# Control_Sense_BOTTMOS_V2.net
KiCad netlist of a schematic drawn in Altium Designer
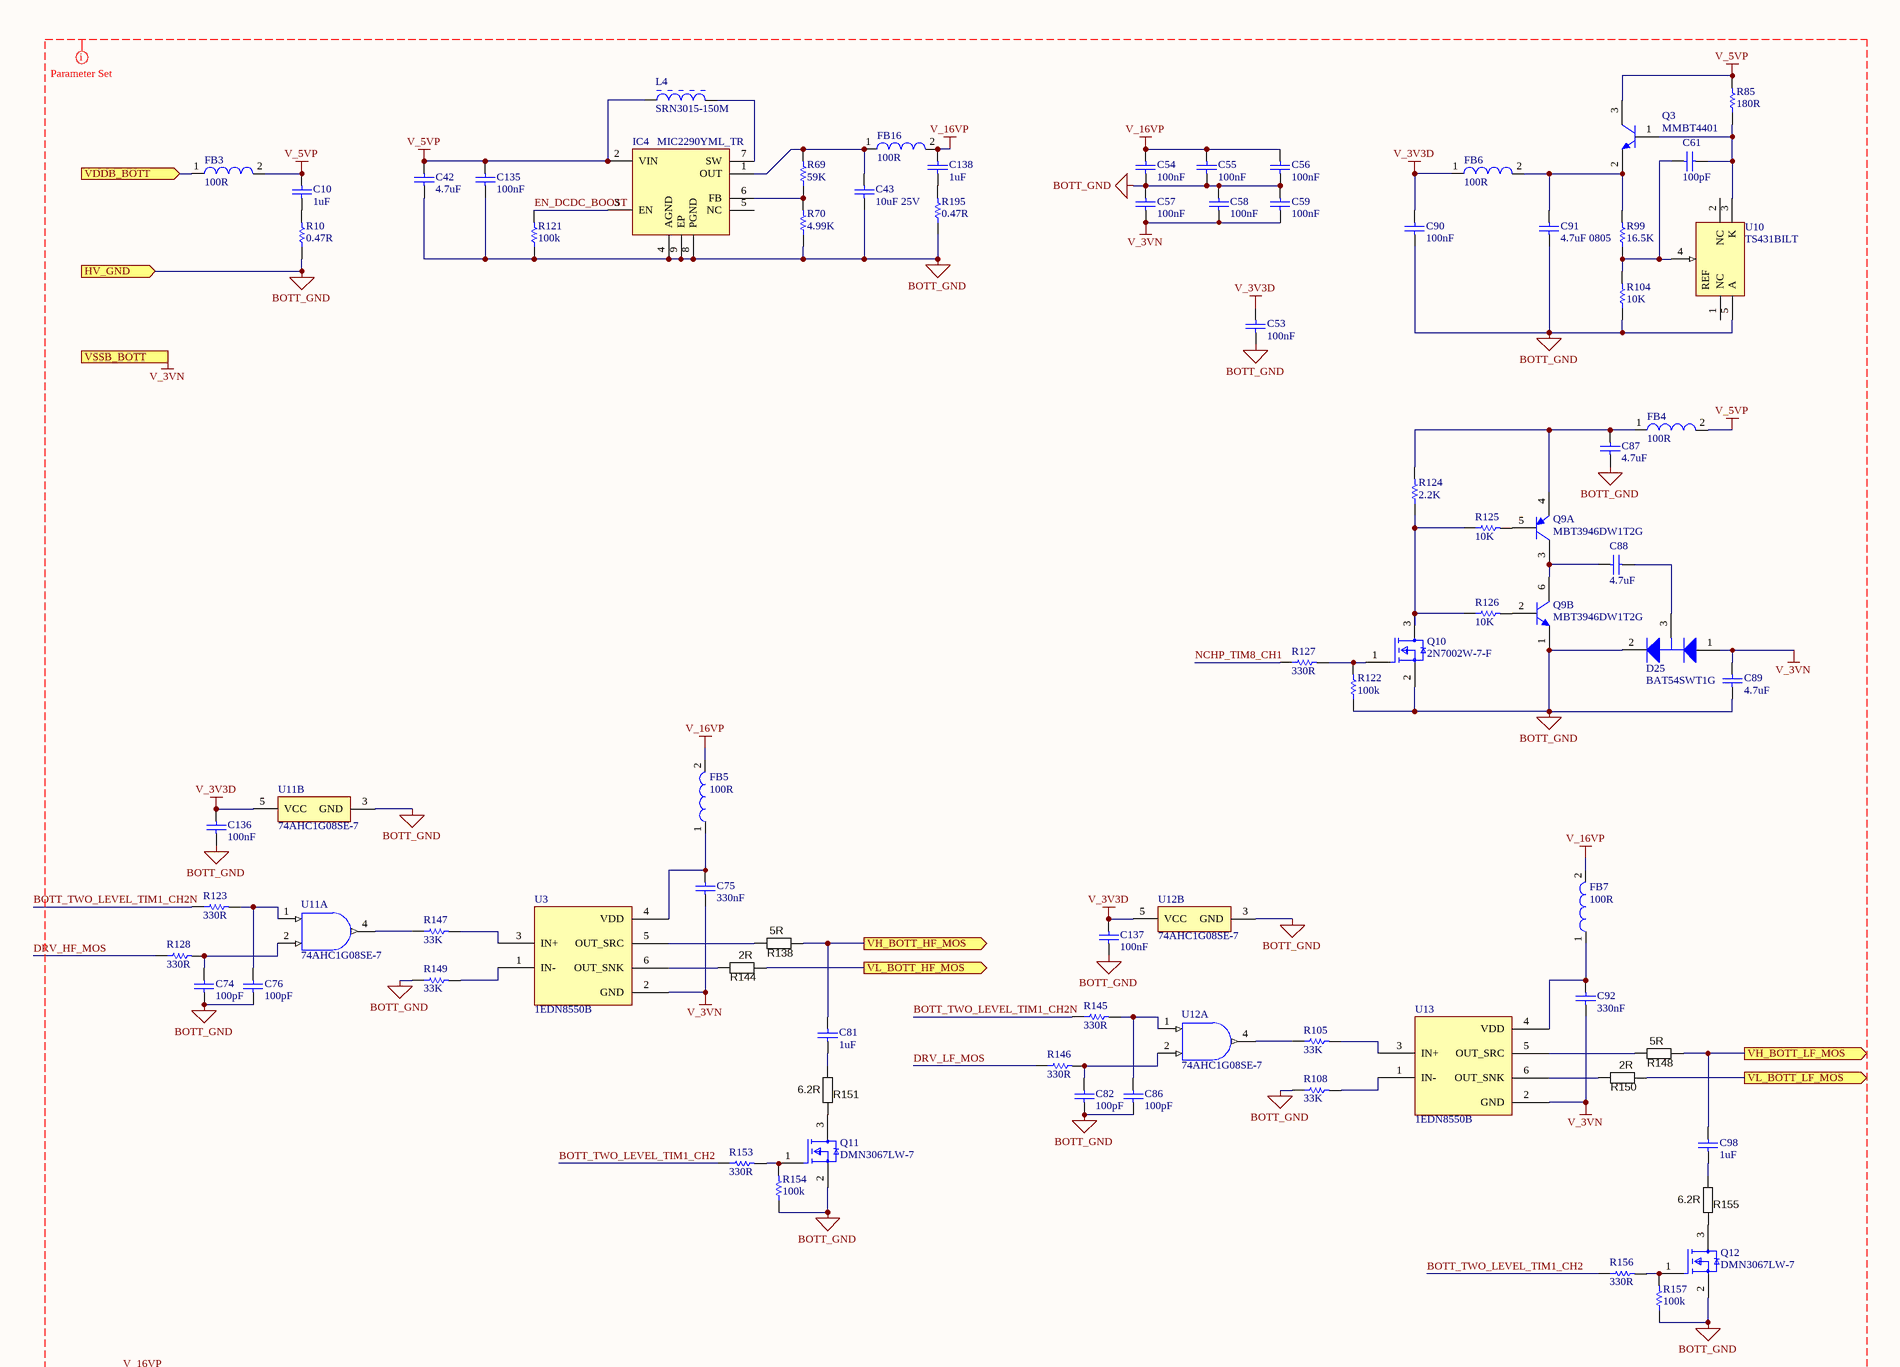
[diagram p0: Control_Sense_BOTTMOS V2.SchDoc, top]
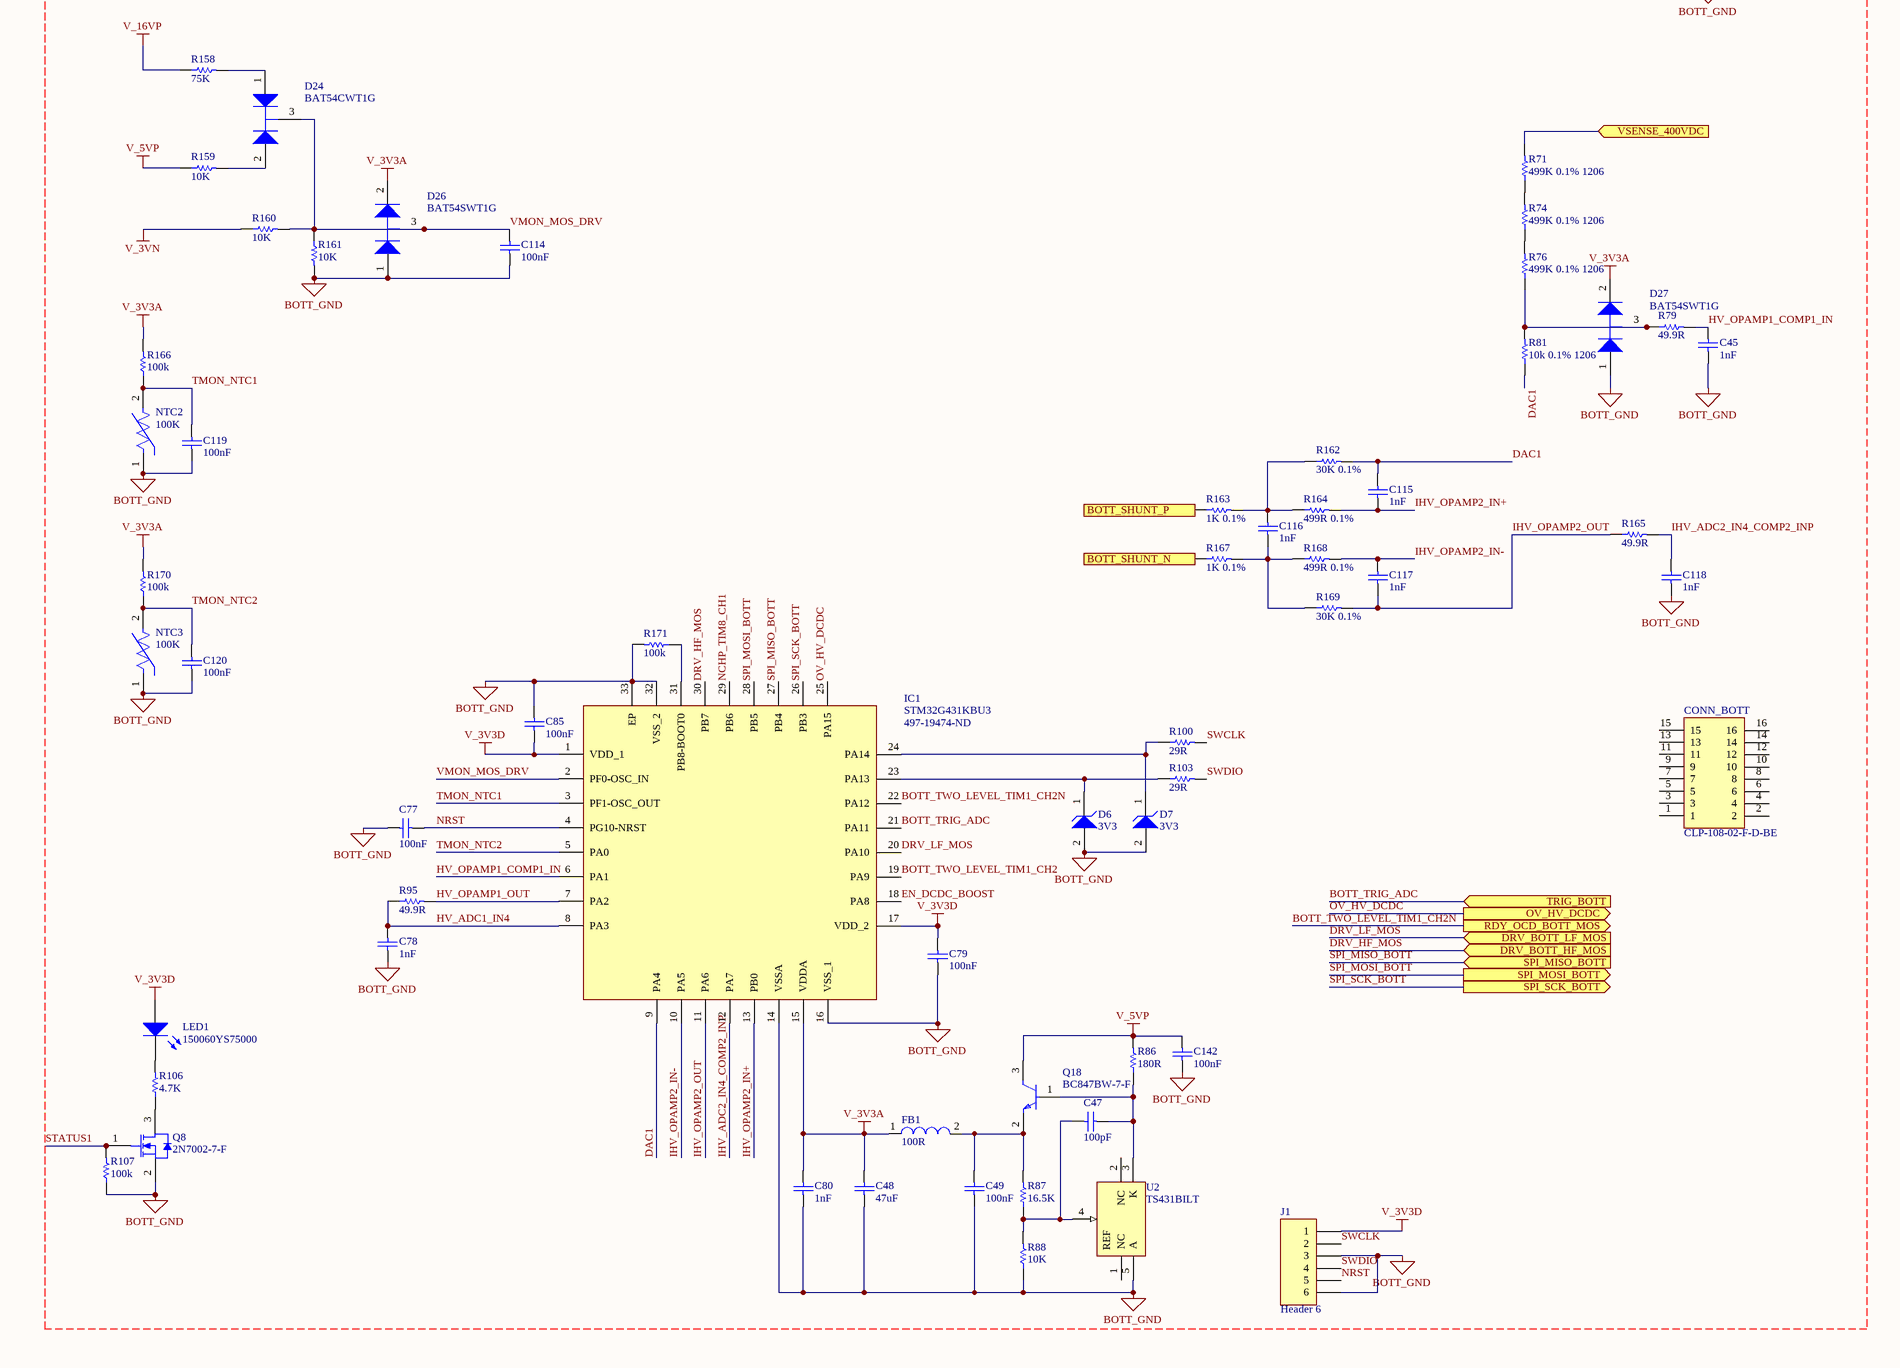
[diagram p1: Control_Sense_BOTTMOS V2.SchDoc, bottom]

(export (version "E")
  (design (tool "Eeschema 10.0.6"))
  (components
    (comp (ref "C10")
      (value "1uF")
      (footprint "CAPC2013X140X50LL20T25")
      (description "SMD Multilayer Ceramic Capacitor, 1 µF, 25 V, 0805 [2012 Metric], ± 10%, X7R")
      (fields (field (name "PART NUMBER") "C0805C105K3RACTU") (field (name "MANUFACTURER") "Kemet"))
      (libsource (lib "Altium Content Vault") (part "CAP"))
    )
    (comp (ref "C42")
      (value "4.7uF")
      (footprint "CAPC2013X145X20NL20")
      (description "Chip Capacitor, 4.7 uF, +/- 10%, 25 V, -55 to 125 degC, 0805 (2012 Metric), RoHS, Tape and Reel")
      (fields (field (name "MANUFACTURER") "TDK") (field (name "TOLERANCE") "±10%"))
      (libsource (lib "Altium Content Vault") (part "CAP-NP-2"))
    )
    (comp (ref "C43")
      (value "10uF 25V")
      (footprint "CAPC3216X229X50LL20T25")
      (description "Chip Capacitor, 10 uF, +/- 10%, 25 V, -55 to 85 degC, 1206 (3216 Metric), RoHS, Tape and Reel")
      (fields (field (name "MANUFACTURER") "AVX"))
      (libsource (lib "Altium Content Vault") (part "CAP-NP-2"))
    )
    (comp (ref "C45")
      (value "1nF")
      (footprint "CAPC1005X56X25LL10T15")
      (fields
        (field (name "MANUFACTURER") "AVX Interconnect / Elco")
        (field (name "PART NUMBER") "04025C102MAT2A")
        (field (name "TOLERANCE") "20%")
      )
      (libsource (lib "Altium Content Vault") (part "CAP"))
    )
    (comp (ref "C47")
      (value "100pF")
      (footprint "CAPC1608X90X35NL10T15")
      (description "0603 100pF 50V ±5 % Tolerance C0G SMT Multilayer Ceramic Capacitor")
      (fields (field (name "PART NUMBER") "GRM1885C1H101JA01D") (field (name "MANUFACTURER") "Murata"))
      (libsource (lib "Altium Content Vault") (part "CAP"))
    )
    (comp (ref "C48")
      (value "47uF")
      (footprint "CAPC2013X145X50LL20T25")
      (fields
        (field (name "MANUFACTURER") "Kemet")
        (field (name "PART NUMBER") "C0805C476M9PACTU")
        (field (name "TOLERANCE") "20%")
      )
      (libsource (lib "Altium Content Vault") (part "CAP"))
    )
    (comp (ref "C49")
      (value "100nF")
      (footprint "SAMS-C0603-2_N")
      (description "Cap Ceramic 0.1uF 50VDC X7R 10% SMD 0603 Paper T/R")
      (fields
        (field (name "MANUFACTURER") "Samsung Electro-Mechanics")
        (field (name "MANUFACTURER PART NUMBER") "CL10B104KB8NNNC")
      )
      (libsource (lib "Altium Content Vault") (part "CAP-NP-2"))
    )
    (comp (ref "C53")
      (value "100nF")
      (footprint "CAPC1608X90X35LL15T15")
      (fields
        (field (name "MANUFACTURER") "AVX Interconnect / Elco")
        (field (name "PART NUMBER") "06035A151JAT2A.")
        (field (name "MANUFACTURER PART NUMBER") "06035A151JAT2A")
      )
      (libsource (lib "Altium Content Vault") (part "CAP"))
    )
    (comp (ref "C54")
      (value "100nF")
      (footprint "CAPC1608X90X35NL15T15")
      (fields
        (field (name "MANUFACTURER") "AVX Interconnect / Elco")
        (field (name "PART NUMBER") "06035A151JAT2A.")
        (field (name "MANUFACTURER PART NUMBER") "06035A151JAT2A")
      )
      (libsource (lib "Altium Content Vault") (part "CAP"))
    )
    (comp (ref "C55")
      (value "100nF")
      (footprint "CAPC1608X90X35NL15T15")
      (fields
        (field (name "MANUFACTURER") "AVX Interconnect / Elco")
        (field (name "PART NUMBER") "06035A151JAT2A.")
        (field (name "MANUFACTURER PART NUMBER") "06035A151JAT2A")
      )
      (libsource (lib "Altium Content Vault") (part "CAP"))
    )
    (comp (ref "C56")
      (value "100nF")
      (footprint "CAPC1608X90X35NL15T15")
      (fields
        (field (name "MANUFACTURER") "AVX Interconnect / Elco")
        (field (name "PART NUMBER") "06035A151JAT2A.")
        (field (name "MANUFACTURER PART NUMBER") "06035A151JAT2A")
      )
      (libsource (lib "Altium Content Vault") (part "CAP"))
    )
    (comp (ref "C57")
      (value "100nF")
      (footprint "CAPC1608X90X35NL15T15")
      (fields
        (field (name "MANUFACTURER") "AVX Interconnect / Elco")
        (field (name "PART NUMBER") "06035A151JAT2A.")
        (field (name "MANUFACTURER PART NUMBER") "06035A151JAT2A")
      )
      (libsource (lib "Altium Content Vault") (part "CAP"))
    )
    (comp (ref "C58")
      (value "100nF")
      (footprint "CAPC1608X90X35NL15T15")
      (fields
        (field (name "MANUFACTURER") "AVX Interconnect / Elco")
        (field (name "PART NUMBER") "06035A151JAT2A.")
        (field (name "MANUFACTURER PART NUMBER") "06035A151JAT2A")
      )
      (libsource (lib "Altium Content Vault") (part "CAP"))
    )
    (comp (ref "C59")
      (value "100nF")
      (footprint "CAPC1608X90X35NL15T15")
      (fields
        (field (name "MANUFACTURER") "AVX Interconnect / Elco")
        (field (name "PART NUMBER") "06035A151JAT2A.")
        (field (name "MANUFACTURER PART NUMBER") "06035A151JAT2A")
      )
      (libsource (lib "Altium Content Vault") (part "CAP"))
    )
    (comp (ref "C61")
      (value "100pF")
      (footprint "CAPC1608X90X35NL10T15")
      (description "0603 100pF 50V ±5 % Tolerance C0G SMT Multilayer Ceramic Capacitor")
      (fields (field (name "PART NUMBER") "GRM1885C1H101JA01D") (field (name "MANUFACTURER") "Murata"))
      (libsource (lib "Altium Content Vault") (part "CAP"))
    )
    (comp (ref "C74")
      (value "100pF")
      (footprint "CAPC1608X90X35NL10T15")
      (fields
        (field (name "PART NUMBER") "GRM1885C1H101JA01D")
        (field (name "MANUFACTURER") "Murata")
        (field (name "TOLERANCE") "5%")
      )
      (libsource (lib "Altium Content Vault") (part "CAP"))
    )
    (comp (ref "C75")
      (value "330nF")
      (footprint "CAPC2013X135X45NL10T25")
      (description "Chip Capacitor, 0.1 uF, +/- 10%, 50 V, -55 to 125 degC, 0805 (2012 Metric), RoHS, Tape and Reel")
      (fields (field (name "VOLTAGE") "50V") (field (name "TOLERANCE") "10%"))
      (libsource (lib "Altium Content Vault") (part "CAP-NP-2"))
    )
    (comp (ref "C76")
      (value "100pF")
      (footprint "CAPC1608X90X35NL10T15")
      (fields
        (field (name "PART NUMBER") "GRM1885C1H101JA01D")
        (field (name "MANUFACTURER") "Murata")
        (field (name "TOLERANCE") "5%")
      )
      (libsource (lib "Altium Content Vault") (part "CAP"))
    )
    (comp (ref "C77")
      (value "100nF")
      (footprint "CAPC1608X90X35LL15T15")
      (fields
        (field (name "MANUFACTURER") "AVX Interconnect / Elco")
        (field (name "PART NUMBER") "06035A151JAT2A.")
        (field (name "MANUFACTURER PART NUMBER") "06035A151JAT2A")
      )
      (libsource (lib "Altium Content Vault") (part "CAP"))
    )
    (comp (ref "C78")
      (value "1nF")
      (footprint "CAPC1005X56X25LL10T15")
      (fields
        (field (name "MANUFACTURER") "AVX Interconnect / Elco")
        (field (name "PART NUMBER") "04025C102MAT2A")
        (field (name "TOLERANCE") "20%")
      )
      (libsource (lib "Altium Content Vault") (part "CAP"))
    )
    (comp (ref "C79")
      (value "100nF")
      (footprint "SAMS-C0603-2_N")
      (description "Cap Ceramic 0.1uF 50VDC X7R 10% SMD 0603 Paper T/R")
      (fields
        (field (name "MANUFACTURER") "Samsung Electro-Mechanics")
        (field (name "MANUFACTURER PART NUMBER") "CL10B104KB8NNNC")
      )
      (libsource (lib "Altium Content Vault") (part "CAP-NP-2"))
    )
    (comp (ref "C80")
      (value "1nF")
      (footprint "CAPC1005X56X25LL10T15")
      (fields
        (field (name "MANUFACTURER") "AVX Interconnect / Elco")
        (field (name "PART NUMBER") "04025C102MAT2A")
        (field (name "TOLERANCE") "20%")
      )
      (libsource (lib "Altium Content Vault") (part "CAP"))
    )
    (comp (ref "C81")
      (value "1uF")
      (footprint "CAPC2013X135X45NL10T25")
      (description "Chip Capacitor, 0.1 uF, +/- 10%, 50 V, -55 to 125 degC, 0805 (2012 Metric), RoHS, Tape and Reel")
      (fields (field (name "VOLTAGE") "50V") (field (name "TOLERANCE") "10%"))
      (libsource (lib "Altium Content Vault") (part "CAP-NP-2"))
    )
    (comp (ref "C82")
      (value "100pF")
      (footprint "CAPC1608X90X35NL10T15")
      (fields
        (field (name "PART NUMBER") "GRM1885C1H101JA01D")
        (field (name "MANUFACTURER") "Murata")
        (field (name "TOLERANCE") "5%")
      )
      (libsource (lib "Altium Content Vault") (part "CAP"))
    )
    (comp (ref "C85")
      (value "100nF")
      (footprint "CAPC1608X90X35LL15T15")
      (fields
        (field (name "MANUFACTURER") "AVX Interconnect / Elco")
        (field (name "PART NUMBER") "06035A151JAT2A.")
        (field (name "MANUFACTURER PART NUMBER") "06035A151JAT2A")
      )
      (libsource (lib "Altium Content Vault") (part "CAP"))
    )
    (comp (ref "C86")
      (value "100pF")
      (footprint "CAPC1608X90X35NL10T15")
      (fields
        (field (name "PART NUMBER") "GRM1885C1H101JA01D")
        (field (name "MANUFACTURER") "Murata")
        (field (name "TOLERANCE") "5%")
      )
      (libsource (lib "Altium Content Vault") (part "CAP"))
    )
    (comp (ref "C87")
      (value "4.7uF")
      (footprint "SAMS-C0603-2_L")
      (description "Cap Ceramic 0.1uF 50VDC X7R 10% SMD 0603 Paper T/R")
      (fields
        (field (name "MANUFACTURER") "Samsung Electro-Mechanics")
        (field (name "MANUFACTURER PART NUMBER") "CL10B104KB8NNNC")
      )
      (libsource (lib "Altium Content Vault") (part "CAP-NP-2"))
    )
    (comp (ref "C88")
      (value "4.7uF")
      (footprint "SAMS-C0603-2_L")
      (description "Cap Ceramic 0.1uF 50VDC X7R 10% SMD 0603 Paper T/R")
      (fields
        (field (name "MANUFACTURER") "Samsung Electro-Mechanics")
        (field (name "MANUFACTURER PART NUMBER") "CL10B104KB8NNNC")
      )
      (libsource (lib "Altium Content Vault") (part "CAP-NP-2"))
    )
    (comp (ref "C89")
      (value "4.7uF")
      (footprint "SAMS-C0603-2_L")
      (description "Cap Ceramic 0.1uF 50VDC X7R 10% SMD 0603 Paper T/R")
      (fields
        (field (name "MANUFACTURER") "Samsung Electro-Mechanics")
        (field (name "MANUFACTURER PART NUMBER") "CL10B104KB8NNNC")
      )
      (libsource (lib "Altium Content Vault") (part "CAP-NP-2"))
    )
    (comp (ref "C90")
      (value "100nF")
      (footprint "SAMS-C0603-2_N")
      (description "Cap Ceramic 0.1uF 50VDC X7R 10% SMD 0603 Paper T/R")
      (fields
        (field (name "MANUFACTURER") "Samsung Electro-Mechanics")
        (field (name "MANUFACTURER PART NUMBER") "CL10B104KB8NNNC")
      )
      (libsource (lib "Altium Content Vault") (part "CAP-NP-2"))
    )
    (comp (ref "C91")
      (value "4.7uF 0805")
      (footprint "CAPC2013X145X20NL20")
      (description "Chip Capacitor, 4.7 uF, +/- 10%, 25 V, -55 to 125 degC, 0805 (2012 Metric), RoHS, Tape and Reel")
      (fields (field (name "MANUFACTURER") "TDK") (field (name "TOLERANCE") "±10%"))
      (libsource (lib "Altium Content Vault") (part "CAP-NP-2"))
    )
    (comp (ref "C92")
      (value "330nF")
      (footprint "CAPC2013X135X45NL10T25")
      (description "Chip Capacitor, 0.1 uF, +/- 10%, 50 V, -55 to 125 degC, 0805 (2012 Metric), RoHS, Tape and Reel")
      (fields (field (name "VOLTAGE") "50V") (field (name "TOLERANCE") "10%"))
      (libsource (lib "Altium Content Vault") (part "CAP-NP-2"))
    )
    (comp (ref "C98")
      (value "1uF")
      (footprint "CAPC2013X135X45NL10T25")
      (description "Chip Capacitor, 0.1 uF, +/- 10%, 50 V, -55 to 125 degC, 0805 (2012 Metric), RoHS, Tape and Reel")
      (fields (field (name "VOLTAGE") "50V") (field (name "TOLERANCE") "10%"))
      (libsource (lib "Altium Content Vault") (part "CAP-NP-2"))
    )
    (comp (ref "C114")
      (value "100nF")
      (footprint "CAPC1608X90X35LL15T15")
      (fields
        (field (name "MANUFACTURER") "AVX Interconnect / Elco")
        (field (name "PART NUMBER") "06035A151JAT2A.")
        (field (name "MANUFACTURER PART NUMBER") "06035A151JAT2A")
      )
      (libsource (lib "Altium Content Vault") (part "CAP"))
    )
    (comp (ref "C115")
      (value "1nF")
      (footprint "CAPC1005X56X25LL10T15")
      (fields
        (field (name "MANUFACTURER") "AVX Interconnect / Elco")
        (field (name "PART NUMBER") "04025C102MAT2A")
        (field (name "TOLERANCE") "20%")
      )
      (libsource (lib "Altium Content Vault") (part "CAP"))
    )
    (comp (ref "C116")
      (value "1nF")
      (footprint "CAPC1608X90X35LL15T15")
      (fields
        (field (name "MANUFACTURER") "AVX Interconnect / Elco")
        (field (name "PART NUMBER") "06035A151JAT2A.")
        (field (name "MANUFACTURER PART NUMBER") "06035A151JAT2A")
      )
      (libsource (lib "Altium Content Vault") (part "CAP"))
    )
    (comp (ref "C117")
      (value "1nF")
      (footprint "CAPC1005X56X25LL10T15")
      (fields
        (field (name "MANUFACTURER") "AVX Interconnect / Elco")
        (field (name "PART NUMBER") "04025C102MAT2A")
        (field (name "TOLERANCE") "20%")
      )
      (libsource (lib "Altium Content Vault") (part "CAP"))
    )
    (comp (ref "C118")
      (value "1nF")
      (footprint "CAPC1005X56X25LL10T15")
      (fields
        (field (name "MANUFACTURER") "AVX Interconnect / Elco")
        (field (name "PART NUMBER") "04025C102MAT2A")
        (field (name "TOLERANCE") "20%")
      )
      (libsource (lib "Altium Content Vault") (part "CAP"))
    )
    (comp (ref "C119")
      (value "100nF")
      (footprint "CAPC1608X90X35LL15T15")
      (fields
        (field (name "MANUFACTURER") "AVX Interconnect / Elco")
        (field (name "PART NUMBER") "06035A151JAT2A.")
        (field (name "MANUFACTURER PART NUMBER") "06035A151JAT2A")
      )
      (libsource (lib "Altium Content Vault") (part "CAP"))
    )
    (comp (ref "C120")
      (value "100nF")
      (footprint "CAPC1608X90X35LL15T15")
      (fields
        (field (name "MANUFACTURER") "AVX Interconnect / Elco")
        (field (name "PART NUMBER") "06035A151JAT2A.")
        (field (name "MANUFACTURER PART NUMBER") "06035A151JAT2A")
      )
      (libsource (lib "Altium Content Vault") (part "CAP"))
    )
    (comp (ref "C135")
      (value "100nF")
      (footprint "CAPC1608X90X35LL15T15")
      (fields
        (field (name "MANUFACTURER") "AVX Interconnect / Elco")
        (field (name "PART NUMBER") "06035A151JAT2A.")
        (field (name "MANUFACTURER PART NUMBER") "06035A151JAT2A")
      )
      (libsource (lib "Altium Content Vault") (part "CAP"))
    )
    (comp (ref "C136")
      (value "100nF")
      (footprint "CAPC1608X90X35LL15T15")
      (fields
        (field (name "MANUFACTURER") "AVX Interconnect / Elco")
        (field (name "PART NUMBER") "06035A151JAT2A.")
        (field (name "MANUFACTURER PART NUMBER") "06035A151JAT2A")
      )
      (libsource (lib "Altium Content Vault") (part "CAP"))
    )
    (comp (ref "C137")
      (value "100nF")
      (footprint "CAPC1608X90X35LL15T15")
      (fields
        (field (name "MANUFACTURER") "AVX Interconnect / Elco")
        (field (name "PART NUMBER") "06035A151JAT2A.")
        (field (name "MANUFACTURER PART NUMBER") "06035A151JAT2A")
      )
      (libsource (lib "Altium Content Vault") (part "CAP"))
    )
    (comp (ref "C138")
      (value "1uF")
      (footprint "CAPC2013X140X50LL20T25")
      (description "SMD Multilayer Ceramic Capacitor, 1 µF, 25 V, 0805 [2012 Metric], ± 10%, X7R")
      (fields (field (name "PART NUMBER") "C0805C105K3RACTU") (field (name "MANUFACTURER") "Kemet"))
      (libsource (lib "Altium Content Vault") (part "CAP"))
    )
    (comp (ref "C142")
      (value "100nF")
      (footprint "SAMS-C0603-2_N")
      (description "Cap Ceramic 0.1uF 50VDC X7R 10% SMD 0603 Paper T/R")
      (fields
        (field (name "MANUFACTURER") "Samsung Electro-Mechanics")
        (field (name "MANUFACTURER PART NUMBER") "CL10B104KB8NNNC")
      )
      (libsource (lib "Altium Content Vault") (part "CAP-NP-2"))
    )
    (comp (ref "CONN_BOTT")
      (value "CLP-108-02-F-D-BE")
      (footprint "SamacSys:CLP-108-02-XXX-D-BE")
      (description "Connector")
      (fields (field (name "MOUSER PART NUMBER") "200-CLP10802FDBE"))
      (libsource (lib "*") (part "CLP-108-02-F-D-BE"))
    )
    (comp (ref "D6")
      (value "3V3")
      (footprint "ONSC-SOD-523-2-502-01_V")
      (fields (field (name "MANUFACTURER") "On Semiconductor") (field (name "PARTNUMBER") "ESD5Z3.3T1G"))
      (libsource (lib "Altium Content Vault") (part "ONSC-K1A2-2"))
    )
    (comp (ref "D7")
      (value "3V3")
      (footprint "ONSC-SOD-523-2-502-01_V")
      (fields (field (name "MANUFACTURER") "On Semiconductor") (field (name "PARTNUMBER") "ESD5Z3.3T1G"))
      (libsource (lib "Altium Content Vault") (part "ONSC-K1A2-2"))
    )
    (comp (ref "D24")
      (value "BAT54CWT1G")
      (footprint "ONSC-SOT-323-3-419-04_V")
      (description "Dual Series Cathode Schottky Barrier Diodes, 3-Pin SOT-323, Pb-Free, Tape and Reel")
      (fields (field (name "MANUFACTURER") "On Semiconductor"))
      (libsource (lib "Altium Content Vault") (part "ONSC-D-A1A2K3-3"))
    )
    (comp (ref "D25")
      (value "BAT54SWT1G")
      (footprint "ONSC-SOT-323-3-419-04_V")
      (description "Dual Series Schottky Barrier Diodes, 3-Pin SOT-323, Pb-Free, Tape and Reel")
      (fields (field (name "MANUFACTURER") "On Semiconductor"))
      (libsource (lib "Altium Content Vault") (part "ONSC-D-A1K2C3-3"))
    )
    (comp (ref "D26")
      (value "BAT54SWT1G")
      (footprint "ONSC-SOT-323-3-419-04_V")
      (description "Dual Series Schottky Barrier Diodes, 3-Pin SOT-323, Pb-Free, Tape and Reel")
      (fields (field (name "MANUFACTURER") "On Semiconductor"))
      (libsource (lib "Altium Content Vault") (part "ONSC-D-A1K2C3-3"))
    )
    (comp (ref "D27")
      (value "BAT54SWT1G")
      (footprint "ONSC-SOT-323-3-419-04_V")
      (description "Dual Series Schottky Barrier Diodes, 3-Pin SOT-323, Pb-Free, Tape and Reel")
      (fields (field (name "MANUFACTURER") "On Semiconductor"))
      (libsource (lib "Altium Content Vault") (part "ONSC-D-A1K2C3-3"))
    )
    (comp (ref "FB1")
      (value "100R")
      (footprint "SMD-0603")
      (description "SMD EMI Suppression Ferrite Bead WE-CBF, Z = 1500 Ohm")
      (libsource (lib "Altium Content Vault") (part "PAS-IND-INDUCTOR-2"))
    )
    (comp (ref "FB3")
      (value "100R")
      (footprint "SMD-0603")
      (description "SMD EMI Suppression Ferrite Bead WE-CBF, Z = 1500 Ohm")
      (libsource (lib "Altium Content Vault") (part "PAS-IND-INDUCTOR-2"))
    )
    (comp (ref "FB4")
      (value "100R")
      (footprint "SMD-0603")
      (description "SMD EMI Suppression Ferrite Bead WE-CBF, Z = 1500 Ohm")
      (libsource (lib "Altium Content Vault") (part "PAS-IND-INDUCTOR-2"))
    )
    (comp (ref "FB5")
      (value "100R")
      (footprint "SMD-0603")
      (description "SMD EMI Suppression Ferrite Bead WE-CBF, Z = 1500 Ohm")
      (libsource (lib "Altium Content Vault") (part "PAS-IND-INDUCTOR-2"))
    )
    (comp (ref "FB6")
      (value "100R")
      (footprint "SMD-0603")
      (description "SMD EMI Suppression Ferrite Bead WE-CBF, Z = 1500 Ohm")
      (libsource (lib "Altium Content Vault") (part "PAS-IND-INDUCTOR-2"))
    )
    (comp (ref "FB7")
      (value "100R")
      (footprint "SMD-0603")
      (description "SMD EMI Suppression Ferrite Bead WE-CBF, Z = 1500 Ohm")
      (libsource (lib "Altium Content Vault") (part "PAS-IND-INDUCTOR-2"))
    )
    (comp (ref "FB16")
      (value "100R")
      (footprint "SMD-0603")
      (description "SMD EMI Suppression Ferrite Bead WE-CBF, Z = 1500 Ohm")
      (libsource (lib "Altium Content Vault") (part "PAS-IND-INDUCTOR-2"))
    )
    (comp (ref "IC1")
      (value "STM32G431KBU3")
      (footprint "SamacSys:QFN50P500X500X60-33N-D")
      (description "Microcontroller 32-Bit ARM Cortex-M4 RISC 128KB Flash 1.71V to 3.6V 32-Pin UFQFPN")
      (fields
        (field (name "MOUSER PART NUMBER") "511-STM32G431KBU3")
        (field (name "MANUFACTURER") "STMicroelectronics")
        (field (name "SUPPLIER PART NUMBER 1") "497-19474-ND")
      )
      (libsource (lib "SamacSys") (part "STM32G431KBU3"))
    )
    (comp (ref "IC4")
      (value "MIC2290YML_TR")
      (footprint "SamacSys:SON50P200X200X95-9N-D")
      (description "Integrated Circuit")
      (fields (field (name "MANUFACTURER_PART_NUMBER") "MIC2290YML TR"))
      (libsource (lib "*") (part "MIC2290YML_TR"))
    )
    (comp (ref "J1")
      (value "Header 6")
      (footprint "HDR1X6")
      (description "Header, 6-Pin")
      (fields (field (name "PUBLISHER") "Altium Limited"))
      (libsource (lib "Miscellaneous Connectors") (part "Header 6"))
    )
    (comp (ref "L4")
      (value "SRN3015-150M")
      (footprint "BOUR-SRN3015-2_V")
      (fields (field (name "MANUFACTURER") "Bourns") (field (name "TOLERANCE") "20%"))
      (libsource (lib "Altium Content Vault") (part "BOUR-IND-2A"))
    )
    (comp (ref "LED1")
      (value "150060YS75000")
      (footprint "0603_A")
      (description "SMD mono-color Chip LED, WL-SMCW, Yellow")
      (fields (field (name "MANUFACTURER") "Wuerth Elektronik"))
      (libsource (lib "Altium Content Vault") (part "WE-LED_K1A2-2"))
    )
    (comp (ref "NTC2")
      (value "100K")
      (footprint "FP-NXR_151B030-MFG")
      (description "Thermistor NTC 10kΩ ±1% 2-Pin Radial Bulk")
      (fields (field (name "TOLERANCE") "1%"))
      (libsource (lib "Altium Content Vault") (part "3b148a6ebabc5fb4d708a66c052d352"))
    )
    (comp (ref "NTC3")
      (value "100K")
      (footprint "FP-NXR_151B030-MFG")
      (description "Thermistor NTC 10kΩ ±1% 2-Pin Radial Bulk")
      (fields (field (name "TOLERANCE") "1%"))
      (libsource (lib "Altium Content Vault") (part "3b148a6ebabc5fb4d708a66c052d352"))
    )
    (comp (ref "Q3")
      (value "MMBT4401")
      (footprint "FAIR-SOT23-3_V")
      (description "NPN General-Purpose Amplifier, 0.6 A, 40 V, -55 to 150 degC, 3-Pin SOT-23, RoHS, Tape and Reel")
      (fields (field (name "MANUFACTURER") "FairchildSemiconductor"))
      (libsource (lib "Altium Content Vault") (part "BJT-NPN-BEC-3"))
    )
    (comp (ref "Q8")
      (value "2N7002-7-F")
      (footprint "DIOD-SOT23-3_V")
      (fields (field (name "MANUFACTURER") "DiodesIncorporated"))
      (libsource (lib "Altium Content Vault") (part "NEMOS-GSD-3"))
    )
    (comp (ref "Q9")
      (value "MBT3946DW1T2G")
      (footprint "ONSC-SC70-6-419B-02_W_V")
      (description "Complementary General Purpose Transistors, 6-Pin SC70, Pb-Free, Tape and Reel")
      (fields (field (name "MANUFACTURER") "On Semiconductor"))
      (libsource (lib "Altium Content Vault") (part "ONSC-NPN_PNP-6"))
    )
    (comp (ref "Q10")
      (value "2N7002W-7-F")
      (footprint "FP-SOT323-IPC_C")
      (description "MOSFET N-CH 60V 115MA SOT323")
      (libsource (lib "Altium Content Vault") (part "381a366367e4312d0f7d2747150cb42"))
    )
    (comp (ref "Q11")
      (value "DMN3067LW-7")
      (footprint "FP-SOT323-IPC_C")
      (description "MOSFET N-CH 60V 115MA SOT323")
      (libsource (lib "Altium Content Vault") (part "381a366367e4312d0f7d2747150cb42"))
    )
    (comp (ref "Q12")
      (value "DMN3067LW-7")
      (footprint "FP-SOT323-IPC_C")
      (description "MOSFET N-CH 60V 115MA SOT323")
      (libsource (lib "Altium Content Vault") (part "381a366367e4312d0f7d2747150cb42"))
    )
    (comp (ref "Q18")
      (value "BC847BW-7-F")
      (footprint "FP-SOT323-IPC_C")
      (description "TRANS NPN 45V 0.1A SC70-3")
      (fields
        (field (name "OCTOPART") "https://octopart.com/bc847bw-7-f-diodes+inc.-354380")
        (field (name "MANUFACTURER") "Diodes Inc")
      )
      (libsource (lib "Altium Content Vault") (part "b44e953556f554d0102664c7d152cb4"))
    )
    (comp (ref "R10")
      (value "0.47R")
      (footprint "RESC1608X55X25ML10T15")
      (description "Chip Resistor, 0 Ohm, +/- 5%, 0.1 W, -55 to 155 degC, 0603 (1608 Metric), RoHS, Tape and Reel")
      (fields (field (name "TOLERANCE") "5%") (field (name "MANUFACTURER") "Yageo"))
      (libsource (lib "Altium Content Vault") (part "RES-2"))
    )
    (comp (ref "R69")
      (value "59K")
      (footprint "RESC1608X55X30NL15T15")
      (fields
        (field (name "MANUFACTURER") "Panasonic")
        (field (name "PART NUMBER") "ERJ-3EKF5902V")
        (field (name "TOLERANCE") "1%")
      )
      (libsource (lib "Altium Content Vault") (part "RES"))
    )
    (comp (ref "R70")
      (value "4.99K")
      (footprint "RESC1609X50X30NL10T20")
      (fields
        (field (name "MANUFACTURER") "Vishay Dale")
        (field (name "PART NUMBER") "CRCW06034K99FKTA")
        (field (name "TOLERANCE") "1%")
      )
      (libsource (lib "Altium Content Vault") (part "RES"))
    )
    (comp (ref "R71")
      (value "499K 0.1% 1206")
      (footprint "RESC3216X50X50NL20T25")
      (description "RES SMD 499K OHM 0.1% 1/4W 1206")
      (fields (field (name "MANUFACTURER") "Susumu") (field (name "PART NUMBER") "RG3216P-4993-B-T1"))
      (libsource (lib "Altium Content Vault") (part "RES"))
    )
    (comp (ref "R74")
      (value "499K 0.1% 1206")
      (footprint "RESC3216X50X50NL20T25")
      (description "RES SMD 499K OHM 0.1% 1/4W 1206")
      (fields (field (name "MANUFACTURER") "Susumu") (field (name "PART NUMBER") "RG3216P-4993-B-T1"))
      (libsource (lib "Altium Content Vault") (part "RES"))
    )
    (comp (ref "R76")
      (value "499K 0.1% 1206")
      (footprint "RESC3216X50X50NL20T25")
      (description "RES SMD 499K OHM 0.1% 1/4W 1206")
      (fields (field (name "MANUFACTURER") "Susumu") (field (name "PART NUMBER") "RG3216P-4993-B-T1"))
      (libsource (lib "Altium Content Vault") (part "RES"))
    )
    (comp (ref "R79")
      (value "49.9R")
      (footprint "RESC1005X40X25NL05T05")
      (fields (field (name "MANUFACTURER") "Panasonic") (field (name "PART NUMBER") "ERJ-2RKF49R9X"))
      (libsource (lib "Altium Content Vault") (part "RES"))
    )
    (comp (ref "R81")
      (value "10k 0.1% 1206")
      (footprint "RESC3216X50X50NL20T20")
      (fields (field (name "MANUFACTURER") "Susumu") (field (name "PART NUMBER") "RG3216P-1002-B-T5"))
      (libsource (lib "Altium Content Vault") (part "RES"))
    )
    (comp (ref "R85")
      (value "180R")
      (footprint "RESC1608X55X25LL10T15")
      (description "Chip Resistor, 180 Ohm, +/- 1%, 0.1 W, -55 to 155 degC, 0603 (1608 Metric), RoHS, Tape and Reel")
      (fields (field (name "TOLERANCE") "1%") (field (name "MANUFACTURER") "Yageo"))
      (libsource (lib "Altium Content Vault") (part "RES-2"))
    )
    (comp (ref "R86")
      (value "180R")
      (footprint "RESC1608X55X25LL10T15")
      (description "Chip Resistor, 180 Ohm, +/- 1%, 0.1 W, -55 to 155 degC, 0603 (1608 Metric), RoHS, Tape and Reel")
      (fields (field (name "TOLERANCE") "1%") (field (name "MANUFACTURER") "Yageo"))
      (libsource (lib "Altium Content Vault") (part "RES-2"))
    )
    (comp (ref "R87")
      (value "16.5K")
      (footprint "RESC1608X55X30NL15T15")
      (description "RES, 16K5, 1%, 0.1W, 0603, THICK FILM")
      (fields (field (name "MANUFACTURER") "Panasonic") (field (name "PART NUMBER") "ERJ-3EKF1652V"))
      (libsource (lib "Altium Content Vault") (part "RES"))
    )
    (comp (ref "R88")
      (value "10K")
      (footprint "RESC1609X55X30NL15T15")
      (description "Chip Resistor, 10 KOhm, +/- 1%, 0.1 W, -55 to 155 degC, 0603 (1608 Metric), RoHS, Tape and Reel")
      (fields (field (name "TOLERANCE") "1%") (field (name "MANUFACTURER") "Panasonic"))
      (libsource (lib "Altium Content Vault") (part "RES-2"))
    )
    (comp (ref "R95")
      (value "49.9R")
      (footprint "RESC1005X40X25NL05T05")
      (fields (field (name "MANUFACTURER") "Panasonic") (field (name "PART NUMBER") "ERJ-2RKF49R9X"))
      (libsource (lib "Altium Content Vault") (part "RES"))
    )
    (comp (ref "R99")
      (value "16.5K")
      (footprint "RESC1608X55X30NL15T15")
      (description "RES, 16K5, 1%, 0.1W, 0603, THICK FILM")
      (fields (field (name "MANUFACTURER") "Panasonic") (field (name "PART NUMBER") "ERJ-3EKF1652V"))
      (libsource (lib "Altium Content Vault") (part "RES"))
    )
    (comp (ref "R100")
      (value "29R")
      (footprint "RESC1608X55X30NL20T10")
      (description "RK73B1JTTD103J")
      (fields (field (name "MANUFACTURER") "KOA Speer") (field (name "TOLERANCE") "5%"))
      (libsource (lib "Altium Content Vault") (part "RES"))
    )
    (comp (ref "R103")
      (value "29R")
      (footprint "RESC1608X55X30NL20T10")
      (description "RK73B1JTTD103J")
      (fields (field (name "MANUFACTURER") "KOA Speer") (field (name "TOLERANCE") "5%"))
      (libsource (lib "Altium Content Vault") (part "RES"))
    )
    (comp (ref "R104")
      (value "10K")
      (footprint "RESC1609X55X30LL15T15")
      (description "Chip Resistor, 10 KOhm, +/- 1%, 0.1 W, -55 to 155 degC, 0603 (1608 Metric), RoHS, Tape and Reel")
      (fields (field (name "TOLERANCE") "1%") (field (name "MANUFACTURER") "Panasonic"))
      (libsource (lib "Altium Content Vault") (part "RES-2"))
    )
    (comp (ref "R105")
      (value "33K")
      (footprint "RESC1005X40X25ML05T05")
      (fields
        (field (name "PART NUMBER") "ERJ2RKF3302X")
        (field (name "MANUFACTURER") "Panasonic")
        (field (name "MANUFACTURER PART NUMBER") "ERJ-2RKF3302X")
      )
      (libsource (lib "Altium Content Vault") (part "RES"))
    )
    (comp (ref "R106")
      (value "4.7K")
      (footprint "RESC1608X55X25ML10T15")
      (fields
        (field (name "MANUFACTURER") "Yageo")
        (field (name "MANUFACTURER PART NUMBER") "RC0603FR-07470RL")
        (field (name "TOLERANCE") "1%")
      )
      (libsource (lib "Altium Content Vault") (part "RES-2"))
    )
    (comp (ref "R107")
      (value "100k")
      (footprint "RESC1608X55X25ML10T15")
      (fields
        (field (name "MANUFACTURER") "Yageo")
        (field (name "MANUFACTURER PART NUMBER") "RC0603JR-071ML")
        (field (name "TOLERANCE") "5%")
      )
      (libsource (lib "Altium Content Vault") (part "RES-2"))
    )
    (comp (ref "R108")
      (value "33K")
      (footprint "RESC1005X40X25ML05T05")
      (fields
        (field (name "PART NUMBER") "ERJ2RKF3302X")
        (field (name "MANUFACTURER") "Panasonic")
        (field (name "MANUFACTURER PART NUMBER") "ERJ-2RKF3302X")
      )
      (libsource (lib "Altium Content Vault") (part "RES"))
    )
    (comp (ref "R121")
      (value "100k")
      (footprint "RESC1608X55X30NL15T15")
      (description "Res Thick Film 0603 100K Ohm 1% 0.1W(1/10W) ±100ppm/C Pad SMD Automotive T/R")
      (fields (field (name "PART NUMBER") "ERJ-3EKF1003V") (field (name "MANUFACTURER") "Panasonic"))
      (libsource (lib "Altium Content Vault") (part "RES"))
    )
    (comp (ref "R122")
      (value "100k")
      (footprint "RESC1608X55X30NL15T15")
      (description "Res Thick Film 0603 100K Ohm 1% 0.1W(1/10W) ±100ppm/C Pad SMD Automotive T/R")
      (fields (field (name "PART NUMBER") "ERJ-3EKF1003V") (field (name "MANUFACTURER") "Panasonic"))
      (libsource (lib "Altium Content Vault") (part "RES"))
    )
    (comp (ref "R123")
      (value "330R")
      (footprint "RESC1608X55X25NL10T15")
      (description "Chip Resistor, 330 Ohm, +/- 1%, 0.1 W, -55 to 155 degC, 0603 (1608 Metric), RoHS, Tape and Reel")
      (fields (field (name "TOLERANCE") "10%"))
      (libsource (lib "Altium Content Vault") (part "RES-2"))
    )
    (comp (ref "R124")
      (value "2.2K")
      (footprint "RESC1608X55X25NL10T15")
      (fields
        (field (name "TOLERANCE") "1%")
        (field (name "MANUFACTURER") "Yageo")
        (field (name "MANUFACTURER PART NUMBER") "RC0603FR-072K2L")
      )
      (libsource (lib "Altium Content Vault") (part "RES-2"))
    )
    (comp (ref "R125")
      (value "10K")
      (footprint "RESC1608X55X30NL20T10")
      (description "RK73B1JTTD103J")
      (fields (field (name "MANUFACTURER") "KOA Speer") (field (name "TOLERANCE") "5%"))
      (libsource (lib "Altium Content Vault") (part "RES"))
    )
    (comp (ref "R126")
      (value "10K")
      (footprint "RESC1608X55X30NL20T10")
      (description "RK73B1JTTD103J")
      (fields (field (name "MANUFACTURER") "KOA Speer") (field (name "TOLERANCE") "5%"))
      (libsource (lib "Altium Content Vault") (part "RES"))
    )
    (comp (ref "R127")
      (value "330R")
      (footprint "RESC1608X55X25NL10T15")
      (description "Chip Resistor, 330 Ohm, +/- 1%, 0.1 W, -55 to 155 degC, 0603 (1608 Metric), RoHS, Tape and Reel")
      (fields (field (name "TOLERANCE") "10%"))
      (libsource (lib "Altium Content Vault") (part "RES-2"))
    )
    (comp (ref "R128")
      (value "330R")
      (footprint "RESC1608X55X25NL10T15")
      (description "Chip Resistor, 330 Ohm, +/- 1%, 0.1 W, -55 to 155 degC, 0603 (1608 Metric), RoHS, Tape and Reel")
      (fields (field (name "TOLERANCE") "10%"))
      (libsource (lib "Altium Content Vault") (part "RES-2"))
    )
    (comp (ref "R138")
      (value "5R")
      (footprint "RESC2012X70N")
      (description "Resistor, 0805 SMD, Empty footprint")
      (libsource (lib "PBL - Resistors") (part "RES_EMPTY_0805"))
    )
    (comp (ref "R144")
      (value "2R")
      (footprint "RESC2012X70N")
      (description "Resistor, 0805 SMD, Empty footprint")
      (libsource (lib "PBL - Resistors") (part "RES_EMPTY_0805"))
    )
    (comp (ref "R145")
      (value "330R")
      (footprint "RESC1608X55X25NL10T15")
      (description "Chip Resistor, 330 Ohm, +/- 1%, 0.1 W, -55 to 155 degC, 0603 (1608 Metric), RoHS, Tape and Reel")
      (fields (field (name "TOLERANCE") "10%"))
      (libsource (lib "Altium Content Vault") (part "RES-2"))
    )
    (comp (ref "R146")
      (value "330R")
      (footprint "RESC1608X55X25NL10T15")
      (description "Chip Resistor, 330 Ohm, +/- 1%, 0.1 W, -55 to 155 degC, 0603 (1608 Metric), RoHS, Tape and Reel")
      (fields (field (name "TOLERANCE") "10%"))
      (libsource (lib "Altium Content Vault") (part "RES-2"))
    )
    (comp (ref "R147")
      (value "33K")
      (footprint "RESC1005X40X25ML05T05")
      (fields
        (field (name "PART NUMBER") "ERJ2RKF3302X")
        (field (name "MANUFACTURER") "Panasonic")
        (field (name "MANUFACTURER PART NUMBER") "ERJ-2RKF3302X")
      )
      (libsource (lib "Altium Content Vault") (part "RES"))
    )
    (comp (ref "R148")
      (value "5R")
      (footprint "RESC2012X70N")
      (description "Resistor, 0805 SMD, Empty footprint")
      (libsource (lib "PBL - Resistors") (part "RES_EMPTY_0805"))
    )
    (comp (ref "R149")
      (value "33K")
      (footprint "RESC1005X40X25ML05T05")
      (fields
        (field (name "PART NUMBER") "ERJ2RKF3302X")
        (field (name "MANUFACTURER") "Panasonic")
        (field (name "MANUFACTURER PART NUMBER") "ERJ-2RKF3302X")
      )
      (libsource (lib "Altium Content Vault") (part "RES"))
    )
    (comp (ref "R150")
      (value "2R")
      (footprint "RESC2012X70N")
      (description "Resistor, 0805 SMD, Empty footprint")
      (libsource (lib "PBL - Resistors") (part "RES_EMPTY_0805"))
    )
    (comp (ref "R151")
      (value "6.2R")
      (footprint "RESC2012X70N")
      (description "Resistor, 0805 SMD, Empty footprint")
      (libsource (lib "") (part "RES_EMPTY_0805_1"))
    )
    (comp (ref "R153")
      (value "330R")
      (footprint "RESC1608X55X25NL10T15")
      (description "Chip Resistor, 330 Ohm, +/- 1%, 0.1 W, -55 to 155 degC, 0603 (1608 Metric), RoHS, Tape and Reel")
      (fields (field (name "TOLERANCE") "10%"))
      (libsource (lib "Altium Content Vault") (part "RES-2"))
    )
    (comp (ref "R154")
      (value "100k")
      (footprint "RESC1608X55X30NL15T15")
      (description "Res Thick Film 0603 100K Ohm 1% 0.1W(1/10W) ±100ppm/C Pad SMD Automotive T/R")
      (fields (field (name "PART NUMBER") "ERJ-3EKF1003V") (field (name "MANUFACTURER") "Panasonic"))
      (libsource (lib "Altium Content Vault") (part "RES"))
    )
    (comp (ref "R155")
      (value "6.2R")
      (footprint "RESC2012X70N")
      (description "Resistor, 0805 SMD, Empty footprint")
      (libsource (lib "") (part "RES_EMPTY_0805_1"))
    )
    (comp (ref "R156")
      (value "330R")
      (footprint "RESC1608X55X25NL10T15")
      (description "Chip Resistor, 330 Ohm, +/- 1%, 0.1 W, -55 to 155 degC, 0603 (1608 Metric), RoHS, Tape and Reel")
      (fields (field (name "TOLERANCE") "10%"))
      (libsource (lib "Altium Content Vault") (part "RES-2"))
    )
    (comp (ref "R157")
      (value "100k")
      (footprint "RESC1608X55X30NL15T15")
      (description "Res Thick Film 0603 100K Ohm 1% 0.1W(1/10W) ±100ppm/C Pad SMD Automotive T/R")
      (fields (field (name "PART NUMBER") "ERJ-3EKF1003V") (field (name "MANUFACTURER") "Panasonic"))
      (libsource (lib "Altium Content Vault") (part "RES"))
    )
    (comp (ref "R158")
      (value "75K")
      (footprint "RESC1608X55X30NL15T15")
      (fields
        (field (name "PART NUMBER") "ERJ-3EKF7502V")
        (field (name "MANUFACTURER") "Panasonic")
        (field (name "TOLERANCE") "1%")
      )
      (libsource (lib "Altium Content Vault") (part "RES"))
    )
    (comp (ref "R159")
      (value "10K")
      (footprint "RESC1608X55X30NL20T10")
      (description "RK73B1JTTD103J")
      (fields (field (name "MANUFACTURER") "KOA Speer") (field (name "TOLERANCE") "5%"))
      (libsource (lib "Altium Content Vault") (part "RES"))
    )
    (comp (ref "R160")
      (value "10K")
      (footprint "RESC1608X55X30NL20T10")
      (description "RK73B1JTTD103J")
      (fields (field (name "MANUFACTURER") "KOA Speer") (field (name "TOLERANCE") "5%"))
      (libsource (lib "Altium Content Vault") (part "RES"))
    )
    (comp (ref "R161")
      (value "10K")
      (footprint "RESC1608X55X30NL20T10")
      (description "RK73B1JTTD103J")
      (fields (field (name "MANUFACTURER") "KOA Speer") (field (name "TOLERANCE") "5%"))
      (libsource (lib "Altium Content Vault") (part "RES"))
    )
    (comp (ref "R162")
      (value "30K 0.1%")
      (footprint "RESC1608X55N")
      (description "Resistor, SMD 30 kOhm 0603  ±  0.1 %, ERA3AEB303V, Panasonic Automotive & Industrial Systems")
      (fields (field (name "MANUFACTURER") "Panasonic") (field (name "PART NUMBER") "ERA3AEB303V"))
      (libsource (lib "PBL - Resistors") (part "RES"))
    )
    (comp (ref "R163")
      (value "1K 0.1%")
      (footprint "RESC1608X55X25NL10T15")
      (description "RES SMD 1K OHM 0.1% 1/10W 0603")
      (fields (field (name "PART NUMBER") "RT0603BRE071KL") (field (name "MANUFACTURER") "Yageo"))
      (libsource (lib "Altium Content Vault") (part "RES"))
    )
    (comp (ref "R164")
      (value "499R 0.1%")
      (footprint "RESC1608X55N")
      (description "Res Thin Film 0603 499 Ohm 0.1% 1/10W ±25ppm/°C Molded SMD SMD Punched Carrier T/R")
      (fields (field (name "PART NUMBER") "ERA3AEB4990V") (field (name "MANUFACTURER") "Panasonic"))
      (libsource (lib "PBL - Resistors") (part "RES"))
    )
    (comp (ref "R165")
      (value "49.9R")
      (footprint "RESC1005X40X25NL05T05")
      (fields (field (name "MANUFACTURER") "Panasonic") (field (name "PART NUMBER") "ERJ-2RKF49R9X"))
      (libsource (lib "Altium Content Vault") (part "RES"))
    )
    (comp (ref "R166")
      (value "100k")
      (footprint "RESC1608X55X30NL15T15")
      (description "Res Thick Film 0603 100K Ohm 1% 0.1W(1/10W) ±100ppm/C Pad SMD Automotive T/R")
      (fields (field (name "PART NUMBER") "ERJ-3EKF1003V") (field (name "MANUFACTURER") "Panasonic"))
      (libsource (lib "Altium Content Vault") (part "RES"))
    )
    (comp (ref "R167")
      (value "1K 0.1%")
      (footprint "RESC1608X55X25NL10T15")
      (description "RES SMD 1K OHM 0.1% 1/10W 0603")
      (fields (field (name "PART NUMBER") "RT0603BRE071KL") (field (name "MANUFACTURER") "Yageo"))
      (libsource (lib "Altium Content Vault") (part "RES"))
    )
    (comp (ref "R168")
      (value "499R 0.1%")
      (footprint "RESC1608X55N")
      (description "Res Thin Film 0603 499 Ohm 0.1% 1/10W ±25ppm/°C Molded SMD SMD Punched Carrier T/R")
      (fields (field (name "PART NUMBER") "ERA3AEB4990V") (field (name "MANUFACTURER") "Panasonic"))
      (libsource (lib "PBL - Resistors") (part "RES"))
    )
    (comp (ref "R169")
      (value "30K 0.1%")
      (footprint "RESC1608X55N")
      (description "Resistor, SMD 30 kOhm 0603  ±  0.1 %, ERA3AEB303V, Panasonic Automotive & Industrial Systems")
      (fields (field (name "MANUFACTURER") "Panasonic") (field (name "PART NUMBER") "ERA3AEB303V"))
      (libsource (lib "PBL - Resistors") (part "RES"))
    )
    (comp (ref "R170")
      (value "100k")
      (footprint "RESC1608X55X30NL15T15")
      (description "Res Thick Film 0603 100K Ohm 1% 0.1W(1/10W) ±100ppm/C Pad SMD Automotive T/R")
      (fields (field (name "PART NUMBER") "ERJ-3EKF1003V") (field (name "MANUFACTURER") "Panasonic"))
      (libsource (lib "Altium Content Vault") (part "RES"))
    )
    (comp (ref "R171")
      (value "100k")
      (footprint "RESC1608X55X30NL15T15")
      (description "Res Thick Film 0603 100K Ohm 1% 0.1W(1/10W) ±100ppm/C Pad SMD Automotive T/R")
      (fields (field (name "PART NUMBER") "ERJ-3EKF1003V") (field (name "MANUFACTURER") "Panasonic"))
      (libsource (lib "Altium Content Vault") (part "RES"))
    )
    (comp (ref "R195")
      (value "0.47R")
      (footprint "RESC1608X55X25ML10T15")
      (description "Chip Resistor, 0 Ohm, +/- 5%, 0.1 W, -55 to 155 degC, 0603 (1608 Metric), RoHS, Tape and Reel")
      (fields (field (name "TOLERANCE") "5%") (field (name "MANUFACTURER") "Yageo"))
      (libsource (lib "Altium Content Vault") (part "RES-2"))
    )
    (comp (ref "U2")
      (value "TS431BILT")
      (footprint "SOT23-5_N")
      (description "30mA, Low voltage adjustable shunt reference, 1.24 to 6V, 5-Pin SOT23-5, Tape and Reel")
      (libsource (lib "Altium Content Vault") (part "PM-REF-431-IL5"))
    )
    (comp (ref "U3")
      (value "1EDN8550B")
      (footprint "SOT23-6")
      (description "Single-channel EiceDRIVER™ with true  differential inputs")
      (libsource (lib "1EDN8550B") (part "1EDN8550B"))
    )
    (comp (ref "U10")
      (value "TS431BILT")
      (footprint "SOT23-5_N")
      (description "30mA, Low voltage adjustable shunt reference, 1.24 to 6V, 5-Pin SOT23-5, Tape and Reel")
      (libsource (lib "Altium Content Vault") (part "PM-REF-431-IL5"))
    )
    (comp (ref "U11")
      (value "74AHC1G08SE-7")
      (footprint "DCK0005A_M")
      (description "Single 2-Input Positive-AND Gate, DCK0005A, SMALL T&R")
      (fields
        (field (name "GENERIC PART NUMBER") "SN74AHC1G08")
        (field (name "MANUFACTURER") "Texas Instruments")
      )
      (libsource (lib "Altium Content Vault") (part "TI-SN74XXX1X08-5"))
    )
    (comp (ref "U12")
      (value "74AHC1G08SE-7")
      (footprint "DCK0005A_M")
      (description "Single 2-Input Positive-AND Gate, DCK0005A, SMALL T&R")
      (fields
        (field (name "GENERIC PART NUMBER") "SN74AHC1G08")
        (field (name "MANUFACTURER") "Texas Instruments")
      )
      (libsource (lib "Altium Content Vault") (part "TI-SN74XXX1X08-5"))
    )
    (comp (ref "U13")
      (value "1EDN8550B")
      (footprint "SOT23-6")
      (description "Single-channel EiceDRIVER™ with true  differential inputs")
      (libsource (lib "1EDN8550B") (part "1EDN8550B"))
    )
  )
  (nets
    (net (code "1") (name "/BOTT_SHUNT_N") (class "Default")
      (node (ref "R167") (pin "1") (pinfunction "1_1") (pintype "passive"))
    )
    (net (code "2") (name "/BOTT_SHUNT_P") (class "Default")
      (node (ref "R163") (pin "1") (pinfunction "1_1") (pintype "passive"))
    )
    (net (code "3") (name "/BOTT_TRIG_ADC") (class "Default")
      (node (ref "IC1") (pin "21") (pinfunction "PA11_21") (pintype "passive"))
    )
    (net (code "4") (name "/BOTT_TWO_LEVEL_TIM1_CH2") (class "Default")
      (node (ref "IC1") (pin "19") (pinfunction "PA9_19") (pintype "passive"))
      (node (ref "R153") (pin "1") (pinfunction "1_1") (pintype "passive"))
      (node (ref "R156") (pin "1") (pinfunction "1_1") (pintype "passive"))
    )
    (net (code "5") (name "/BOTT_TWO_LEVEL_TIM1_CH2N") (class "Default")
      (node (ref "IC1") (pin "22") (pinfunction "PA12_22") (pintype "passive"))
      (node (ref "R123") (pin "1") (pinfunction "1_1") (pintype "passive"))
      (node (ref "R145") (pin "1") (pinfunction "1_1") (pintype "passive"))
    )
    (net (code "6") (name "/DAC1") (class "Default")
      (node (ref "C115") (pin "2") (pinfunction "2_2") (pintype "passive"))
      (node (ref "IC1") (pin "9") (pinfunction "PA4_9") (pintype "passive"))
      (node (ref "R162") (pin "2") (pinfunction "2_2") (pintype "passive"))
      (node (ref "R81") (pin "1") (pinfunction "1_1") (pintype "passive"))
    )
    (net (code "7") (name "/DRV_HF_MOS") (class "Default")
      (node (ref "IC1") (pin "30") (pinfunction "PB7_30") (pintype "passive"))
      (node (ref "R128") (pin "1") (pinfunction "1_1") (pintype "passive"))
    )
    (net (code "8") (name "/DRV_LF_MOS") (class "Default")
      (node (ref "IC1") (pin "20") (pinfunction "PA10_20") (pintype "passive"))
      (node (ref "R146") (pin "1") (pinfunction "1_1") (pintype "passive"))
    )
    (net (code "9") (name "/EN_DCDC_BOOST") (class "Default")
      (node (ref "IC1") (pin "18") (pinfunction "PA8_18") (pintype "passive"))
      (node (ref "IC4") (pin "3") (pinfunction "EN_3") (pintype "passive"))
      (node (ref "R121") (pin "2") (pinfunction "2_2") (pintype "passive"))
    )
    (net (code "10") (name "/HV_ADC1_IN4") (class "Default")
      (node (ref "C78") (pin "2") (pinfunction "2_2") (pintype "passive"))
      (node (ref "IC1") (pin "8") (pinfunction "PA3_8") (pintype "passive"))
      (node (ref "R95") (pin "1") (pinfunction "1_1") (pintype "passive"))
    )
    (net (code "11") (name "/HV_OPAMP1_COMP1_IN") (class "Default")
      (node (ref "C45") (pin "2") (pinfunction "2_2") (pintype "passive"))
      (node (ref "IC1") (pin "6") (pinfunction "PA1_6") (pintype "passive"))
      (node (ref "R79") (pin "2") (pinfunction "2_2") (pintype "passive"))
    )
    (net (code "12") (name "/HV_OPAMP1_OUT") (class "Default")
      (node (ref "IC1") (pin "7") (pinfunction "PA2_7") (pintype "passive"))
      (node (ref "R95") (pin "2") (pinfunction "2_2") (pintype "passive"))
    )
    (net (code "13") (name "/IHV_ADC2_IN4_COMP2_INP") (class "Default")
      (node (ref "C118") (pin "2") (pinfunction "2_2") (pintype "passive"))
      (node (ref "IC1") (pin "12") (pinfunction "PA7_12") (pintype "passive"))
      (node (ref "R165") (pin "2") (pinfunction "2_2") (pintype "passive"))
    )
    (net (code "14") (name "/IHV_OPAMP2_IN+") (class "Default")
      (node (ref "C115") (pin "1") (pinfunction "1_1") (pintype "passive"))
      (node (ref "IC1") (pin "13") (pinfunction "PB0_13") (pintype "passive"))
      (node (ref "R164") (pin "2") (pinfunction "2_2") (pintype "passive"))
    )
    (net (code "15") (name "/IHV_OPAMP2_IN-") (class "Default")
      (node (ref "C117") (pin "2") (pinfunction "2_2") (pintype "passive"))
      (node (ref "IC1") (pin "10") (pinfunction "PA5_10") (pintype "passive"))
      (node (ref "R168") (pin "2") (pinfunction "2_2") (pintype "passive"))
    )
    (net (code "16") (name "/IHV_OPAMP2_OUT") (class "Default")
      (node (ref "C117") (pin "1") (pinfunction "1_1") (pintype "passive"))
      (node (ref "IC1") (pin "11") (pinfunction "PA6_11") (pintype "passive"))
      (node (ref "R165") (pin "1") (pinfunction "1_1") (pintype "passive"))
      (node (ref "R169") (pin "2") (pinfunction "2_2") (pintype "passive"))
    )
    (net (code "17") (name "/NCHP_TIM8_CH1") (class "Default")
      (node (ref "IC1") (pin "29") (pinfunction "PB6_29") (pintype "passive"))
      (node (ref "R127") (pin "1") (pinfunction "1_1") (pintype "passive"))
    )
    (net (code "18") (name "/NRST") (class "Default")
      (node (ref "C77") (pin "2") (pinfunction "2_2") (pintype "passive"))
      (node (ref "IC1") (pin "4") (pinfunction "PG10-NRST_4") (pintype "passive"))
      (node (ref "J1") (pin "5") (pinfunction "5_5") (pintype "passive"))
    )
    (net (code "19") (name "/OV_HV_DCDC") (class "Default")
      (node (ref "IC1") (pin "25") (pinfunction "PA15_25") (pintype "passive"))
    )
    (net (code "20") (name "/SPI_MISO_BOTT") (class "Default")
      (node (ref "IC1") (pin "27") (pinfunction "PB4_27") (pintype "passive"))
    )
    (net (code "21") (name "/SPI_MOSI_BOTT") (class "Default")
      (node (ref "IC1") (pin "28") (pinfunction "PB5_28") (pintype "passive"))
    )
    (net (code "22") (name "/SPI_SCK_BOTT") (class "Default")
      (node (ref "IC1") (pin "26") (pinfunction "PB3_26") (pintype "passive"))
    )
    (net (code "23") (name "/STATUS1") (class "Default")
      (node (ref "Q8") (pin "1") (pinfunction "G_1") (pintype "passive"))
      (node (ref "R107") (pin "2") (pinfunction "2_2") (pintype "passive"))
    )
    (net (code "24") (name "/SWCLK") (class "Default")
      (node (ref "J1") (pin "2") (pinfunction "2_2") (pintype "passive"))
      (node (ref "R100") (pin "2") (pinfunction "2_2") (pintype "passive"))
    )
    (net (code "25") (name "/SWDIO") (class "Default")
      (node (ref "J1") (pin "4") (pinfunction "4_4") (pintype "passive"))
      (node (ref "R103") (pin "2") (pinfunction "2_2") (pintype "passive"))
    )
    (net (code "26") (name "/TMON_NTC1") (class "Default")
      (node (ref "C119") (pin "2") (pinfunction "2_2") (pintype "passive"))
      (node (ref "IC1") (pin "3") (pinfunction "PF1-OSC_OUT_3") (pintype "passive"))
      (node (ref "NTC2") (pin "2") (pinfunction "2_2") (pintype "passive"))
      (node (ref "R166") (pin "1") (pinfunction "1_1") (pintype "passive"))
    )
    (net (code "27") (name "/TMON_NTC2") (class "Default")
      (node (ref "C120") (pin "2") (pinfunction "2_2") (pintype "passive"))
      (node (ref "IC1") (pin "5") (pinfunction "PA0_5") (pintype "passive"))
      (node (ref "NTC3") (pin "2") (pinfunction "2_2") (pintype "passive"))
      (node (ref "R170") (pin "1") (pinfunction "1_1") (pintype "passive"))
    )
    (net (code "28") (name "/VDDB_BOTT") (class "Default")
      (node (ref "FB3") (pin "1") (pinfunction "1_1") (pintype "passive"))
    )
    (net (code "29") (name "/VH_BOTT_HF_MOS") (class "Default")
      (node (ref "C81") (pin "2") (pinfunction "2_2") (pintype "passive"))
      (node (ref "R138") (pin "2") (pinfunction "2_2") (pintype "passive"))
    )
    (net (code "30") (name "/VH_BOTT_LF_MOS") (class "Default")
      (node (ref "C98") (pin "2") (pinfunction "2_2") (pintype "passive"))
      (node (ref "R148") (pin "2") (pinfunction "2_2") (pintype "passive"))
    )
    (net (code "31") (name "/VL_BOTT_HF_MOS") (class "Default")
      (node (ref "R144") (pin "2") (pinfunction "2_2") (pintype "passive"))
    )
    (net (code "32") (name "/VL_BOTT_LF_MOS") (class "Default")
      (node (ref "R150") (pin "2") (pinfunction "2_2") (pintype "passive"))
    )
    (net (code "33") (name "/VMON_MOS_DRV") (class "Default")
      (node (ref "C114") (pin "2") (pinfunction "2_2") (pintype "passive"))
      (node (ref "D24") (pin "3") (pinfunction "K_3") (pintype "passive"))
      (node (ref "D26") (pin "3") (pinfunction "K/A_3") (pintype "passive"))
      (node (ref "IC1") (pin "2") (pinfunction "PF0-OSC_IN_2") (pintype "passive"))
      (node (ref "R160") (pin "2") (pinfunction "2_2") (pintype "passive"))
      (node (ref "R161") (pin "1") (pinfunction "1_1") (pintype "passive"))
    )
    (net (code "34") (name "/VSENSE_400VDC") (class "Default")
      (node (ref "R71") (pin "2") (pinfunction "2_2") (pintype "passive"))
    )
    (net (code "35") (name "BOTT_GND") (class "Default")
      (node (ref "C114") (pin "1") (pinfunction "1_1") (pintype "passive"))
      (node (ref "C118") (pin "1") (pinfunction "1_1") (pintype "passive"))
      (node (ref "C119") (pin "1") (pinfunction "1_1") (pintype "passive"))
      (node (ref "C120") (pin "1") (pinfunction "1_1") (pintype "passive"))
      (node (ref "C135") (pin "1") (pinfunction "1_1") (pintype "passive"))
      (node (ref "C136") (pin "1") (pinfunction "1_1") (pintype "passive"))
      (node (ref "C137") (pin "1") (pinfunction "1_1") (pintype "passive"))
      (node (ref "C142") (pin "1") (pinfunction "1_1") (pintype "passive"))
      (node (ref "C42") (pin "1") (pinfunction "1_1") (pintype "passive"))
      (node (ref "C43") (pin "1") (pinfunction "1_1") (pintype "passive"))
      (node (ref "C45") (pin "1") (pinfunction "1_1") (pintype "passive"))
      (node (ref "C48") (pin "1") (pinfunction "1_1") (pintype "passive"))
      (node (ref "C49") (pin "1") (pinfunction "1_1") (pintype "passive"))
      (node (ref "C53") (pin "1") (pinfunction "1_1") (pintype "passive"))
      (node (ref "C54") (pin "1") (pinfunction "1_1") (pintype "passive"))
      (node (ref "C55") (pin "1") (pinfunction "1_1") (pintype "passive"))
      (node (ref "C56") (pin "1") (pinfunction "1_1") (pintype "passive"))
      (node (ref "C57") (pin "2") (pinfunction "2_2") (pintype "passive"))
      (node (ref "C58") (pin "2") (pinfunction "2_2") (pintype "passive"))
      (node (ref "C59") (pin "2") (pinfunction "2_2") (pintype "passive"))
      (node (ref "C74") (pin "1") (pinfunction "1_1") (pintype "passive"))
      (node (ref "C76") (pin "1") (pinfunction "1_1") (pintype "passive"))
      (node (ref "C77") (pin "1") (pinfunction "1_1") (pintype "passive"))
      (node (ref "C78") (pin "1") (pinfunction "1_1") (pintype "passive"))
      (node (ref "C79") (pin "1") (pinfunction "1_1") (pintype "passive"))
      (node (ref "C80") (pin "1") (pinfunction "1_1") (pintype "passive"))
      (node (ref "C82") (pin "1") (pinfunction "1_1") (pintype "passive"))
      (node (ref "C85") (pin "2") (pinfunction "2_2") (pintype "passive"))
      (node (ref "C86") (pin "1") (pinfunction "1_1") (pintype "passive"))
      (node (ref "C87") (pin "1") (pinfunction "1_1") (pintype "passive"))
      (node (ref "C89") (pin "1") (pinfunction "1_1") (pintype "passive"))
      (node (ref "C90") (pin "1") (pinfunction "1_1") (pintype "passive"))
      (node (ref "C91") (pin "1") (pinfunction "1_1") (pintype "passive"))
      (node (ref "D25") (pin "2") (pinfunction "K_2") (pintype "passive"))
      (node (ref "D26") (pin "1") (pinfunction "A_1") (pintype "passive"))
      (node (ref "D27") (pin "1") (pinfunction "A_1") (pintype "passive"))
      (node (ref "D6") (pin "2") (pinfunction "A_2") (pintype "passive"))
      (node (ref "D7") (pin "2") (pinfunction "A_2") (pintype "passive"))
      (node (ref "IC1") (pin "14") (pinfunction "VSSA_14") (pintype "passive"))
      (node (ref "IC1") (pin "16") (pinfunction "VSS_1_16") (pintype "passive"))
      (node (ref "IC1") (pin "32") (pinfunction "VSS_2_32") (pintype "passive"))
      (node (ref "IC1") (pin "33") (pinfunction "EP_33") (pintype "passive"))
      (node (ref "IC4") (pin "4") (pinfunction "AGND_4") (pintype "passive"))
      (node (ref "IC4") (pin "8") (pinfunction "PGND_8") (pintype "passive"))
      (node (ref "IC4") (pin "9") (pinfunction "EP_9") (pintype "passive"))
      (node (ref "J1") (pin "3") (pinfunction "3_3") (pintype "passive"))
      (node (ref "J1") (pin "6") (pinfunction "6_6") (pintype "passive"))
      (node (ref "NTC2") (pin "1") (pinfunction "1_1") (pintype "passive"))
      (node (ref "NTC3") (pin "1") (pinfunction "1_1") (pintype "passive"))
      (node (ref "Q10") (pin "2") (pinfunction "S_2") (pintype "passive"))
      (node (ref "Q11") (pin "2") (pinfunction "S_2") (pintype "passive"))
      (node (ref "Q12") (pin "2") (pinfunction "S_2") (pintype "passive"))
      (node (ref "Q8") (pin "2") (pinfunction "S_2") (pintype "passive"))
      (node (ref "Q9") (pin "1") (pinfunction "E_1") (pintype "passive"))
      (node (ref "R10") (pin "1") (pinfunction "1_1") (pintype "passive"))
      (node (ref "R104") (pin "1") (pinfunction "1_1") (pintype "passive"))
      (node (ref "R107") (pin "1") (pinfunction "1_1") (pintype "passive"))
      (node (ref "R108") (pin "1") (pinfunction "1_1") (pintype "passive"))
      (node (ref "R121") (pin "1") (pinfunction "1_1") (pintype "passive"))
      (node (ref "R122") (pin "1") (pinfunction "1_1") (pintype "passive"))
      (node (ref "R149") (pin "1") (pinfunction "1_1") (pintype "passive"))
      (node (ref "R154") (pin "1") (pinfunction "1_1") (pintype "passive"))
      (node (ref "R157") (pin "1") (pinfunction "1_1") (pintype "passive"))
      (node (ref "R161") (pin "2") (pinfunction "2_2") (pintype "passive"))
      (node (ref "R171") (pin "2") (pinfunction "2_2") (pintype "passive"))
      (node (ref "R195") (pin "1") (pinfunction "1_1") (pintype "passive"))
      (node (ref "R70") (pin "1") (pinfunction "1_1") (pintype "passive"))
      (node (ref "R88") (pin "1") (pinfunction "1_1") (pintype "passive"))
      (node (ref "U10") (pin "5") (pinfunction "A_5") (pintype "passive"))
      (node (ref "U11") (pin "3") (pinfunction "GND_3") (pintype "power_in"))
      (node (ref "U12") (pin "3") (pinfunction "GND_3") (pintype "power_in"))
      (node (ref "U2") (pin "5") (pinfunction "A_5") (pintype "passive"))
    )
    (net (code "36") (name "Net-(C10-Pad1)") (class "Default")
      (node (ref "C10") (pin "1") (pinfunction "1_1") (pintype "passive"))
      (node (ref "R10") (pin "2") (pinfunction "2_2") (pintype "passive"))
    )
    (net (code "37") (name "Net-(C81-Pad1)") (class "Default")
      (node (ref "C81") (pin "1") (pinfunction "1_1") (pintype "passive"))
      (node (ref "R151") (pin "2") (pinfunction "2_2") (pintype "passive"))
    )
    (net (code "38") (name "Net-(C98-Pad1)") (class "Default")
      (node (ref "C98") (pin "1") (pinfunction "1_1") (pintype "passive"))
      (node (ref "R155") (pin "2") (pinfunction "2_2") (pintype "passive"))
    )
    (net (code "39") (name "Net-(C116-Pad1)") (class "Default")
      (node (ref "C116") (pin "1") (pinfunction "1_1") (pintype "passive"))
      (node (ref "R167") (pin "2") (pinfunction "2_2") (pintype "passive"))
      (node (ref "R168") (pin "1") (pinfunction "1_1") (pintype "passive"))
      (node (ref "R169") (pin "1") (pinfunction "1_1") (pintype "passive"))
    )
    (net (code "40") (name "Net-(C116-Pad2)") (class "Default")
      (node (ref "C116") (pin "2") (pinfunction "2_2") (pintype "passive"))
      (node (ref "R162") (pin "1") (pinfunction "1_1") (pintype "passive"))
      (node (ref "R163") (pin "2") (pinfunction "2_2") (pintype "passive"))
      (node (ref "R164") (pin "1") (pinfunction "1_1") (pintype "passive"))
    )
    (net (code "41") (name "Net-(C138-Pad1)") (class "Default")
      (node (ref "C138") (pin "1") (pinfunction "1_1") (pintype "passive"))
      (node (ref "R195") (pin "2") (pinfunction "2_2") (pintype "passive"))
    )
    (net (code "42") (name "Net-(D6-K)") (class "Default")
      (node (ref "D6") (pin "1") (pinfunction "K_1") (pintype "passive"))
      (node (ref "IC1") (pin "23") (pinfunction "PA13_23") (pintype "passive"))
      (node (ref "R103") (pin "1") (pinfunction "1_1") (pintype "passive"))
    )
    (net (code "43") (name "Net-(D7-K)") (class "Default")
      (node (ref "D7") (pin "1") (pinfunction "K_1") (pintype "passive"))
      (node (ref "IC1") (pin "24") (pinfunction "PA14_24") (pintype "passive"))
      (node (ref "R100") (pin "1") (pinfunction "1_1") (pintype "passive"))
    )
    (net (code "44") (name "Net-(D24-A1)") (class "Default")
      (node (ref "D24") (pin "1") (pinfunction "A1_1") (pintype "passive"))
      (node (ref "R158") (pin "2") (pinfunction "2_2") (pintype "passive"))
    )
    (net (code "45") (name "Net-(D24-A2)") (class "Default")
      (node (ref "D24") (pin "2") (pinfunction "A2_2") (pintype "passive"))
      (node (ref "R159") (pin "2") (pinfunction "2_2") (pintype "passive"))
    )
    (net (code "46") (name "Net-(D25-K{slash}A)") (class "Default")
      (node (ref "C88") (pin "1") (pinfunction "1_1") (pintype "passive"))
      (node (ref "D25") (pin "3") (pinfunction "K/A_3") (pintype "passive"))
    )
    (net (code "47") (name "Net-(D27-K{slash}A)") (class "Default")
      (node (ref "D27") (pin "3") (pinfunction "K/A_3") (pintype "passive"))
      (node (ref "R76") (pin "1") (pinfunction "1_1") (pintype "passive"))
      (node (ref "R79") (pin "1") (pinfunction "1_1") (pintype "passive"))
      (node (ref "R81") (pin "2") (pinfunction "2_2") (pintype "passive"))
    )
    (net (code "48") (name "Net-(IC1-PB8-BOOT0)") (class "Default")
      (node (ref "IC1") (pin "31") (pinfunction "PB8-BOOT0_31") (pintype "passive"))
      (node (ref "R171") (pin "1") (pinfunction "1_1") (pintype "passive"))
    )
    (net (code "49") (name "Net-(IC4-FB)") (class "Default")
      (node (ref "IC4") (pin "6") (pinfunction "FB_6") (pintype "passive"))
      (node (ref "R69") (pin "1") (pinfunction "1_1") (pintype "passive"))
      (node (ref "R70") (pin "2") (pinfunction "2_2") (pintype "passive"))
    )
    (net (code "50") (name "Net-(IC4-OUT)") (class "Default")
      (node (ref "C43") (pin "2") (pinfunction "2_2") (pintype "passive"))
      (node (ref "FB16") (pin "1") (pinfunction "1_1") (pintype "passive"))
      (node (ref "IC4") (pin "1") (pinfunction "OUT_1") (pintype "passive"))
      (node (ref "R69") (pin "2") (pinfunction "2_2") (pintype "passive"))
    )
    (net (code "51") (name "Net-(IC4-SW)") (class "Default")
      (node (ref "IC4") (pin "7") (pinfunction "SW_7") (pintype "passive"))
      (node (ref "L4") (pin "2") (pinfunction "2_2") (pintype "passive"))
    )
    (net (code "52") (name "Net-(LED1-K)") (class "Default")
      (node (ref "LED1") (pin "1") (pinfunction "K_1") (pintype "passive"))
      (node (ref "R106") (pin "2") (pinfunction "2_2") (pintype "passive"))
    )
    (net (code "53") (name "Net-(Q3-B)") (class "Default")
      (node (ref "C61") (pin "2") (pinfunction "2_2") (pintype "passive"))
      (node (ref "Q3") (pin "1") (pinfunction "B_1") (pintype "passive"))
      (node (ref "R85") (pin "1") (pinfunction "1_1") (pintype "passive"))
      (node (ref "U10") (pin "3") (pinfunction "K_3") (pintype "passive"))
    )
    (net (code "54") (name "Net-(Q3-E)") (class "Default")
      (node (ref "C91") (pin "2") (pinfunction "2_2") (pintype "passive"))
      (node (ref "FB6") (pin "2") (pinfunction "2_2") (pintype "passive"))
      (node (ref "Q3") (pin "2") (pinfunction "E_2") (pintype "passive"))
      (node (ref "R99") (pin "2") (pinfunction "2_2") (pintype "passive"))
    )
    (net (code "55") (name "Net-(Q8-D)") (class "Default")
      (node (ref "Q8") (pin "3") (pinfunction "D_3") (pintype "passive"))
      (node (ref "R106") (pin "1") (pinfunction "1_1") (pintype "passive"))
    )
    (net (code "56") (name "Net-(Q9A-B)") (class "Default")
      (node (ref "Q9") (pin "5") (pinfunction "B_5") (pintype "passive"))
      (node (ref "R125") (pin "2") (pinfunction "2_2") (pintype "passive"))
    )
    (net (code "57") (name "Net-(Q9A-C)") (class "Default")
      (node (ref "C88") (pin "2") (pinfunction "2_2") (pintype "passive"))
      (node (ref "Q9") (pin "3") (pinfunction "C_3") (pintype "passive"))
      (node (ref "Q9") (pin "6") (pinfunction "C_6") (pintype "passive"))
    )
    (net (code "58") (name "Net-(Q9A-E)") (class "Default")
      (node (ref "C87") (pin "2") (pinfunction "2_2") (pintype "passive"))
      (node (ref "FB4") (pin "1") (pinfunction "1_1") (pintype "passive"))
      (node (ref "Q9") (pin "4") (pinfunction "E_4") (pintype "passive"))
      (node (ref "R124") (pin "2") (pinfunction "2_2") (pintype "passive"))
    )
    (net (code "59") (name "Net-(Q9B-B)") (class "Default")
      (node (ref "Q9") (pin "2") (pinfunction "B_2") (pintype "passive"))
      (node (ref "R126") (pin "2") (pinfunction "2_2") (pintype "passive"))
    )
    (net (code "60") (name "Net-(Q10-D)") (class "Default")
      (node (ref "Q10") (pin "3") (pinfunction "D_3") (pintype "passive"))
      (node (ref "R124") (pin "1") (pinfunction "1_1") (pintype "passive"))
      (node (ref "R125") (pin "1") (pinfunction "1_1") (pintype "passive"))
      (node (ref "R126") (pin "1") (pinfunction "1_1") (pintype "passive"))
    )
    (net (code "61") (name "Net-(Q10-G)") (class "Default")
      (node (ref "Q10") (pin "1") (pinfunction "G_1") (pintype "passive"))
      (node (ref "R122") (pin "2") (pinfunction "2_2") (pintype "passive"))
      (node (ref "R127") (pin "2") (pinfunction "2_2") (pintype "passive"))
    )
    (net (code "62") (name "Net-(Q11-D)") (class "Default")
      (node (ref "Q11") (pin "3") (pinfunction "D_3") (pintype "passive"))
      (node (ref "R151") (pin "1") (pinfunction "1_1") (pintype "passive"))
    )
    (net (code "63") (name "Net-(Q11-G)") (class "Default")
      (node (ref "Q11") (pin "1") (pinfunction "G_1") (pintype "passive"))
      (node (ref "R153") (pin "2") (pinfunction "2_2") (pintype "passive"))
      (node (ref "R154") (pin "2") (pinfunction "2_2") (pintype "passive"))
    )
    (net (code "64") (name "Net-(Q12-D)") (class "Default")
      (node (ref "Q12") (pin "3") (pinfunction "D_3") (pintype "passive"))
      (node (ref "R155") (pin "1") (pinfunction "1_1") (pintype "passive"))
    )
    (net (code "65") (name "Net-(Q12-G)") (class "Default")
      (node (ref "Q12") (pin "1") (pinfunction "G_1") (pintype "passive"))
      (node (ref "R156") (pin "2") (pinfunction "2_2") (pintype "passive"))
      (node (ref "R157") (pin "2") (pinfunction "2_2") (pintype "passive"))
    )
    (net (code "66") (name "Net-(Q18-B)") (class "Default")
      (node (ref "C47") (pin "2") (pinfunction "2_2") (pintype "passive"))
      (node (ref "Q18") (pin "1") (pinfunction "B_1") (pintype "passive"))
      (node (ref "R86") (pin "1") (pinfunction "1_1") (pintype "passive"))
      (node (ref "U2") (pin "3") (pinfunction "K_3") (pintype "passive"))
    )
    (net (code "67") (name "Net-(Q18-E)") (class "Default")
      (node (ref "C49") (pin "2") (pinfunction "2_2") (pintype "passive"))
      (node (ref "FB1") (pin "2") (pinfunction "2_2") (pintype "passive"))
      (node (ref "Q18") (pin "2") (pinfunction "E_2") (pintype "passive"))
      (node (ref "R87") (pin "2") (pinfunction "2_2") (pintype "passive"))
    )
    (net (code "68") (name "Net-(R71-Pad1)") (class "Default")
      (node (ref "R71") (pin "1") (pinfunction "1_1") (pintype "passive"))
      (node (ref "R74") (pin "2") (pinfunction "2_2") (pintype "passive"))
    )
    (net (code "69") (name "Net-(R74-Pad1)") (class "Default")
      (node (ref "R74") (pin "1") (pinfunction "1_1") (pintype "passive"))
      (node (ref "R76") (pin "2") (pinfunction "2_2") (pintype "passive"))
    )
    (net (code "70") (name "Net-(U2-REF)") (class "Default")
      (node (ref "C47") (pin "1") (pinfunction "1_1") (pintype "passive"))
      (node (ref "R87") (pin "1") (pinfunction "1_1") (pintype "passive"))
      (node (ref "R88") (pin "2") (pinfunction "2_2") (pintype "passive"))
      (node (ref "U2") (pin "4") (pinfunction "REF_4") (pintype "input"))
    )
    (net (code "71") (name "Net-(U3-IN+)") (class "Default")
      (node (ref "R147") (pin "2") (pinfunction "2_2") (pintype "passive"))
      (node (ref "U3") (pin "3") (pinfunction "IN+_3") (pintype "passive"))
    )
    (net (code "72") (name "Net-(U3-IN-)") (class "Default")
      (node (ref "R149") (pin "2") (pinfunction "2_2") (pintype "passive"))
      (node (ref "U3") (pin "1") (pinfunction "IN-_1") (pintype "passive"))
    )
    (net (code "73") (name "Net-(U3-OUT_SNK)") (class "Default")
      (node (ref "R144") (pin "1") (pinfunction "1_1") (pintype "passive"))
      (node (ref "U3") (pin "6") (pinfunction "OUT_SNK_6") (pintype "passive"))
    )
    (net (code "74") (name "Net-(U3-OUT_SRC)") (class "Default")
      (node (ref "R138") (pin "1") (pinfunction "1_1") (pintype "passive"))
      (node (ref "U3") (pin "5") (pinfunction "OUT_SRC_5") (pintype "passive"))
    )
    (net (code "75") (name "Net-(U3-VDD)") (class "Default")
      (node (ref "C75") (pin "2") (pinfunction "2_2") (pintype "passive"))
      (node (ref "FB5") (pin "1") (pinfunction "1_1") (pintype "passive"))
      (node (ref "U3") (pin "4") (pinfunction "VDD_4") (pintype "passive"))
    )
    (net (code "76") (name "Net-(U10-REF)") (class "Default")
      (node (ref "C61") (pin "1") (pinfunction "1_1") (pintype "passive"))
      (node (ref "R104") (pin "2") (pinfunction "2_2") (pintype "passive"))
      (node (ref "R99") (pin "1") (pinfunction "1_1") (pintype "passive"))
      (node (ref "U10") (pin "4") (pinfunction "REF_4") (pintype "input"))
    )
    (net (code "77") (name "Net-(U11A-A)") (class "Default")
      (node (ref "C76") (pin "2") (pinfunction "2_2") (pintype "passive"))
      (node (ref "R123") (pin "2") (pinfunction "2_2") (pintype "passive"))
      (node (ref "U11") (pin "1") (pinfunction "A_1") (pintype "input"))
    )
    (net (code "78") (name "Net-(U11A-B)") (class "Default")
      (node (ref "C74") (pin "2") (pinfunction "2_2") (pintype "passive"))
      (node (ref "R128") (pin "2") (pinfunction "2_2") (pintype "passive"))
      (node (ref "U11") (pin "2") (pinfunction "B_2") (pintype "input"))
    )
    (net (code "79") (name "Net-(U11A-Y)") (class "Default")
      (node (ref "R147") (pin "1") (pinfunction "1_1") (pintype "passive"))
      (node (ref "U11") (pin "4") (pinfunction "Y_4") (pintype "output"))
    )
    (net (code "80") (name "Net-(U12A-A)") (class "Default")
      (node (ref "C86") (pin "2") (pinfunction "2_2") (pintype "passive"))
      (node (ref "R145") (pin "2") (pinfunction "2_2") (pintype "passive"))
      (node (ref "U12") (pin "1") (pinfunction "A_1") (pintype "input"))
    )
    (net (code "81") (name "Net-(U12A-B)") (class "Default")
      (node (ref "C82") (pin "2") (pinfunction "2_2") (pintype "passive"))
      (node (ref "R146") (pin "2") (pinfunction "2_2") (pintype "passive"))
      (node (ref "U12") (pin "2") (pinfunction "B_2") (pintype "input"))
    )
    (net (code "82") (name "Net-(U12A-Y)") (class "Default")
      (node (ref "R105") (pin "1") (pinfunction "1_1") (pintype "passive"))
      (node (ref "U12") (pin "4") (pinfunction "Y_4") (pintype "output"))
    )
    (net (code "83") (name "Net-(U13-IN+)") (class "Default")
      (node (ref "R105") (pin "2") (pinfunction "2_2") (pintype "passive"))
      (node (ref "U13") (pin "3") (pinfunction "IN+_3") (pintype "passive"))
    )
    (net (code "84") (name "Net-(U13-IN-)") (class "Default")
      (node (ref "R108") (pin "2") (pinfunction "2_2") (pintype "passive"))
      (node (ref "U13") (pin "1") (pinfunction "IN-_1") (pintype "passive"))
    )
    (net (code "85") (name "Net-(U13-OUT_SNK)") (class "Default")
      (node (ref "R150") (pin "1") (pinfunction "1_1") (pintype "passive"))
      (node (ref "U13") (pin "6") (pinfunction "OUT_SNK_6") (pintype "passive"))
    )
    (net (code "86") (name "Net-(U13-OUT_SRC)") (class "Default")
      (node (ref "R148") (pin "1") (pinfunction "1_1") (pintype "passive"))
      (node (ref "U13") (pin "5") (pinfunction "OUT_SRC_5") (pintype "passive"))
    )
    (net (code "87") (name "Net-(U13-VDD)") (class "Default")
      (node (ref "C92") (pin "2") (pinfunction "2_2") (pintype "passive"))
      (node (ref "FB7") (pin "1") (pinfunction "1_1") (pintype "passive"))
      (node (ref "U13") (pin "4") (pinfunction "VDD_4") (pintype "passive"))
    )
    (net (code "88") (name "V_3V3A") (class "Default")
      (node (ref "C48") (pin "2") (pinfunction "2_2") (pintype "passive"))
      (node (ref "C80") (pin "2") (pinfunction "2_2") (pintype "passive"))
      (node (ref "D26") (pin "2") (pinfunction "K_2") (pintype "passive"))
      (node (ref "D27") (pin "2") (pinfunction "K_2") (pintype "passive"))
      (node (ref "FB1") (pin "1") (pinfunction "1_1") (pintype "passive"))
      (node (ref "IC1") (pin "15") (pinfunction "VDDA_15") (pintype "passive"))
      (node (ref "R166") (pin "2") (pinfunction "2_2") (pintype "passive"))
      (node (ref "R170") (pin "2") (pinfunction "2_2") (pintype "passive"))
    )
    (net (code "89") (name "V_3V3D") (class "Default")
      (node (ref "C136") (pin "2") (pinfunction "2_2") (pintype "passive"))
      (node (ref "C137") (pin "2") (pinfunction "2_2") (pintype "passive"))
      (node (ref "C53") (pin "2") (pinfunction "2_2") (pintype "passive"))
      (node (ref "C79") (pin "2") (pinfunction "2_2") (pintype "passive"))
      (node (ref "C85") (pin "1") (pinfunction "1_1") (pintype "passive"))
      (node (ref "C90") (pin "2") (pinfunction "2_2") (pintype "passive"))
      (node (ref "FB6") (pin "1") (pinfunction "1_1") (pintype "passive"))
      (node (ref "IC1") (pin "1") (pinfunction "VDD_1_1") (pintype "passive"))
      (node (ref "IC1") (pin "17") (pinfunction "VDD_2_17") (pintype "passive"))
      (node (ref "J1") (pin "1") (pinfunction "1_1") (pintype "passive"))
      (node (ref "LED1") (pin "2") (pinfunction "A_2") (pintype "passive"))
      (node (ref "U11") (pin "5") (pinfunction "VCC_5") (pintype "power_in"))
      (node (ref "U12") (pin "5") (pinfunction "VCC_5") (pintype "power_in"))
    )
    (net (code "90") (name "V_3VN") (class "Default")
      (node (ref "C57") (pin "1") (pinfunction "1_1") (pintype "passive"))
      (node (ref "C58") (pin "1") (pinfunction "1_1") (pintype "passive"))
      (node (ref "C59") (pin "1") (pinfunction "1_1") (pintype "passive"))
      (node (ref "C75") (pin "1") (pinfunction "1_1") (pintype "passive"))
      (node (ref "C89") (pin "2") (pinfunction "2_2") (pintype "passive"))
      (node (ref "C92") (pin "1") (pinfunction "1_1") (pintype "passive"))
      (node (ref "D25") (pin "1") (pinfunction "A_1") (pintype "passive"))
      (node (ref "R160") (pin "1") (pinfunction "1_1") (pintype "passive"))
      (node (ref "U13") (pin "2") (pinfunction "GND_2") (pintype "passive"))
      (node (ref "U3") (pin "2") (pinfunction "GND_2") (pintype "passive"))
    )
    (net (code "91") (name "V_5VP") (class "Default")
      (node (ref "C10") (pin "2") (pinfunction "2_2") (pintype "passive"))
      (node (ref "C135") (pin "2") (pinfunction "2_2") (pintype "passive"))
      (node (ref "C142") (pin "2") (pinfunction "2_2") (pintype "passive"))
      (node (ref "C42") (pin "2") (pinfunction "2_2") (pintype "passive"))
      (node (ref "FB3") (pin "2") (pinfunction "2_2") (pintype "passive"))
      (node (ref "FB4") (pin "2") (pinfunction "2_2") (pintype "passive"))
      (node (ref "IC4") (pin "2") (pinfunction "VIN_2") (pintype "passive"))
      (node (ref "L4") (pin "1") (pinfunction "1_1") (pintype "passive"))
      (node (ref "Q18") (pin "3") (pinfunction "C_3") (pintype "passive"))
      (node (ref "Q3") (pin "3") (pinfunction "C_3") (pintype "passive"))
      (node (ref "R159") (pin "1") (pinfunction "1_1") (pintype "passive"))
      (node (ref "R85") (pin "2") (pinfunction "2_2") (pintype "passive"))
      (node (ref "R86") (pin "2") (pinfunction "2_2") (pintype "passive"))
    )
    (net (code "92") (name "V_16VP") (class "Default")
      (node (ref "C138") (pin "2") (pinfunction "2_2") (pintype "passive"))
      (node (ref "C54") (pin "2") (pinfunction "2_2") (pintype "passive"))
      (node (ref "C55") (pin "2") (pinfunction "2_2") (pintype "passive"))
      (node (ref "C56") (pin "2") (pinfunction "2_2") (pintype "passive"))
      (node (ref "FB16") (pin "2") (pinfunction "2_2") (pintype "passive"))
      (node (ref "FB5") (pin "2") (pinfunction "2_2") (pintype "passive"))
      (node (ref "FB7") (pin "2") (pinfunction "2_2") (pintype "passive"))
      (node (ref "R158") (pin "1") (pinfunction "1_1") (pintype "passive"))
    )
    (net (code "93") (name "unconnected-(CONN_BOTT-Pad1)") (class "Default")
      (node (ref "CONN_BOTT") (pin "1") (pinfunction "1_1") (pintype "passive"))
    )
    (net (code "94") (name "unconnected-(CONN_BOTT-Pad2)") (class "Default")
      (node (ref "CONN_BOTT") (pin "2") (pinfunction "2_2") (pintype "passive"))
    )
    (net (code "95") (name "unconnected-(CONN_BOTT-Pad3)") (class "Default")
      (node (ref "CONN_BOTT") (pin "3") (pinfunction "3_3") (pintype "passive"))
    )
    (net (code "96") (name "unconnected-(CONN_BOTT-Pad4)") (class "Default")
      (node (ref "CONN_BOTT") (pin "4") (pinfunction "4_4") (pintype "passive"))
    )
    (net (code "97") (name "unconnected-(CONN_BOTT-Pad5)") (class "Default")
      (node (ref "CONN_BOTT") (pin "5") (pinfunction "5_5") (pintype "passive"))
    )
    (net (code "98") (name "unconnected-(CONN_BOTT-Pad6)") (class "Default")
      (node (ref "CONN_BOTT") (pin "6") (pinfunction "6_6") (pintype "passive"))
    )
    (net (code "99") (name "unconnected-(CONN_BOTT-Pad7)") (class "Default")
      (node (ref "CONN_BOTT") (pin "7") (pinfunction "7_7") (pintype "passive"))
    )
    (net (code "100") (name "unconnected-(CONN_BOTT-Pad8)") (class "Default")
      (node (ref "CONN_BOTT") (pin "8") (pinfunction "8_8") (pintype "passive"))
    )
    (net (code "101") (name "unconnected-(CONN_BOTT-Pad9)") (class "Default")
      (node (ref "CONN_BOTT") (pin "9") (pinfunction "9_9") (pintype "passive"))
    )
    (net (code "102") (name "unconnected-(CONN_BOTT-Pad10)") (class "Default")
      (node (ref "CONN_BOTT") (pin "10") (pinfunction "10_10") (pintype "passive"))
    )
    (net (code "103") (name "unconnected-(CONN_BOTT-Pad11)") (class "Default")
      (node (ref "CONN_BOTT") (pin "11") (pinfunction "11_11") (pintype "passive"))
    )
    (net (code "104") (name "unconnected-(CONN_BOTT-Pad12)") (class "Default")
      (node (ref "CONN_BOTT") (pin "12") (pinfunction "12_12") (pintype "passive"))
    )
    (net (code "105") (name "unconnected-(CONN_BOTT-Pad13)") (class "Default")
      (node (ref "CONN_BOTT") (pin "13") (pinfunction "13_13") (pintype "passive"))
    )
    (net (code "106") (name "unconnected-(CONN_BOTT-Pad14)") (class "Default")
      (node (ref "CONN_BOTT") (pin "14") (pinfunction "14_14") (pintype "passive"))
    )
    (net (code "107") (name "unconnected-(CONN_BOTT-Pad15)") (class "Default")
      (node (ref "CONN_BOTT") (pin "15") (pinfunction "15_15") (pintype "passive"))
    )
    (net (code "108") (name "unconnected-(CONN_BOTT-Pad16)") (class "Default")
      (node (ref "CONN_BOTT") (pin "16") (pinfunction "16_16") (pintype "passive"))
    )
    (net (code "109") (name "unconnected-(IC4-NC-Pad5)") (class "Default")
      (node (ref "IC4") (pin "5") (pinfunction "NC_5") (pintype "passive"))
    )
    (net (code "110") (name "unconnected-(U2-NC-Pad1)") (class "Default")
      (node (ref "U2") (pin "1") (pinfunction "NC_1") (pintype "passive"))
    )
    (net (code "111") (name "unconnected-(U2-NC-Pad2)") (class "Default")
      (node (ref "U2") (pin "2") (pinfunction "NC_2") (pintype "passive"))
    )
    (net (code "112") (name "unconnected-(U10-NC-Pad1)") (class "Default")
      (node (ref "U10") (pin "1") (pinfunction "NC_1") (pintype "passive"))
    )
    (net (code "113") (name "unconnected-(U10-NC-Pad2)") (class "Default")
      (node (ref "U10") (pin "2") (pinfunction "NC_2") (pintype "passive"))
    )
  )
)
